# ab_v10_panel.net
KiCad netlist of a schematic drawn in EAGLE
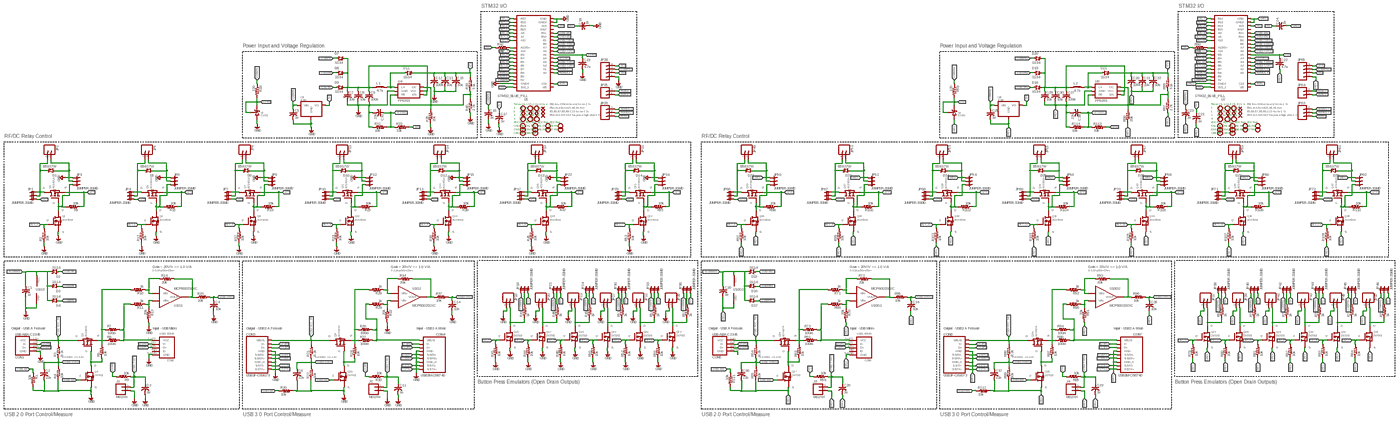
[diagram p0: schematic, sheet 1, overview]
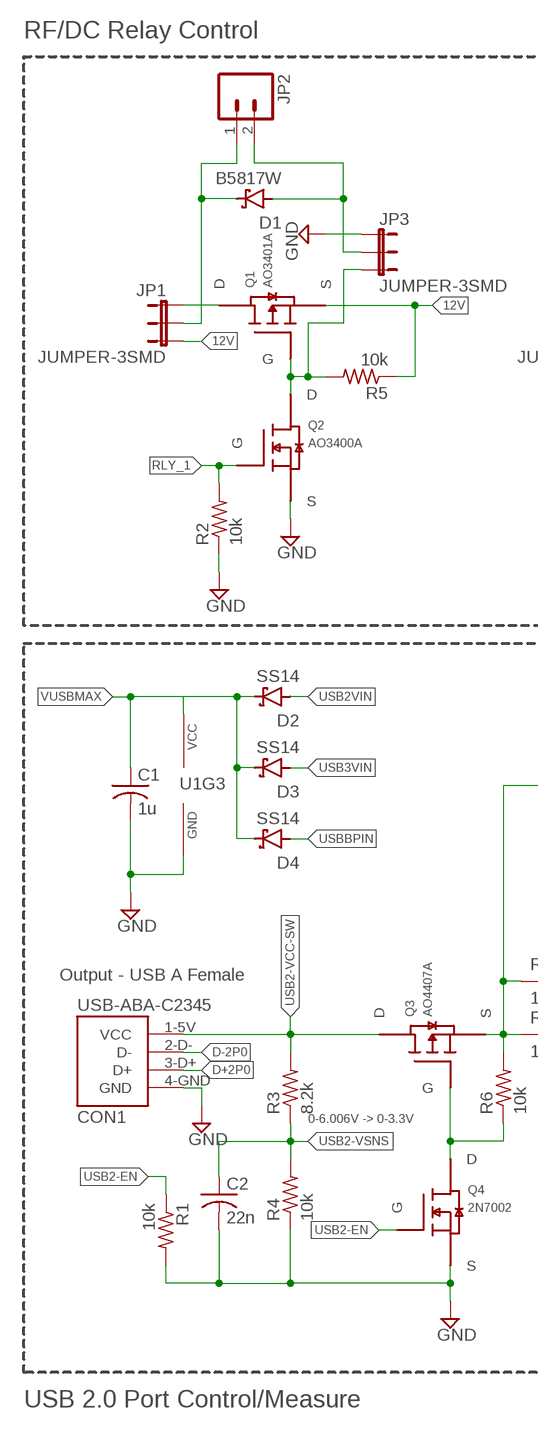
[diagram p1: schematic, sheet 1, part 1 of 4]
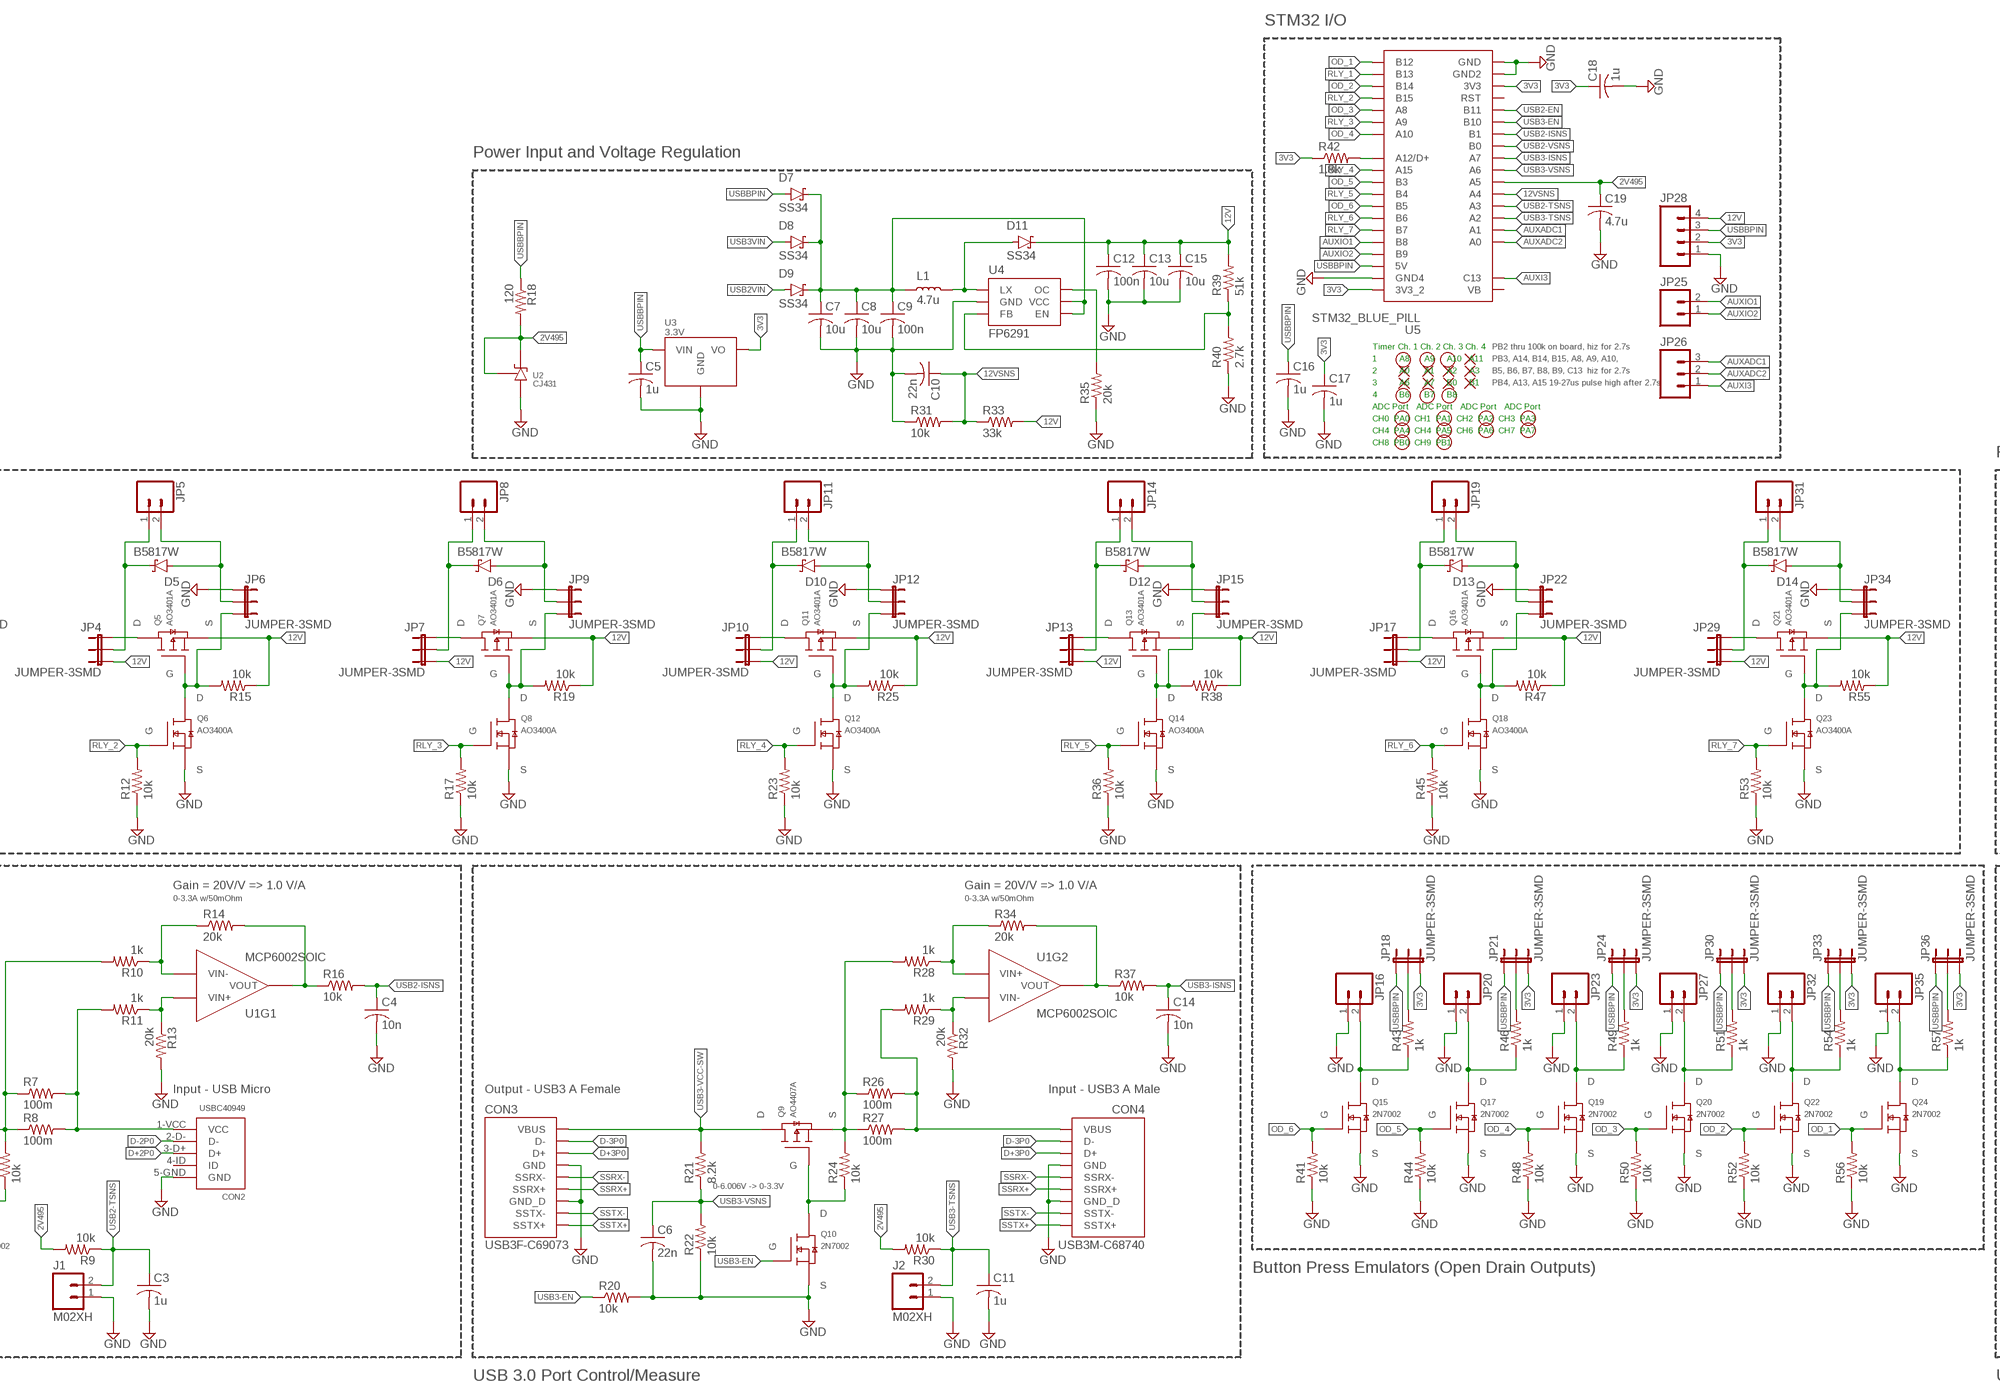
[diagram p2: schematic, sheet 1, part 2 of 4]
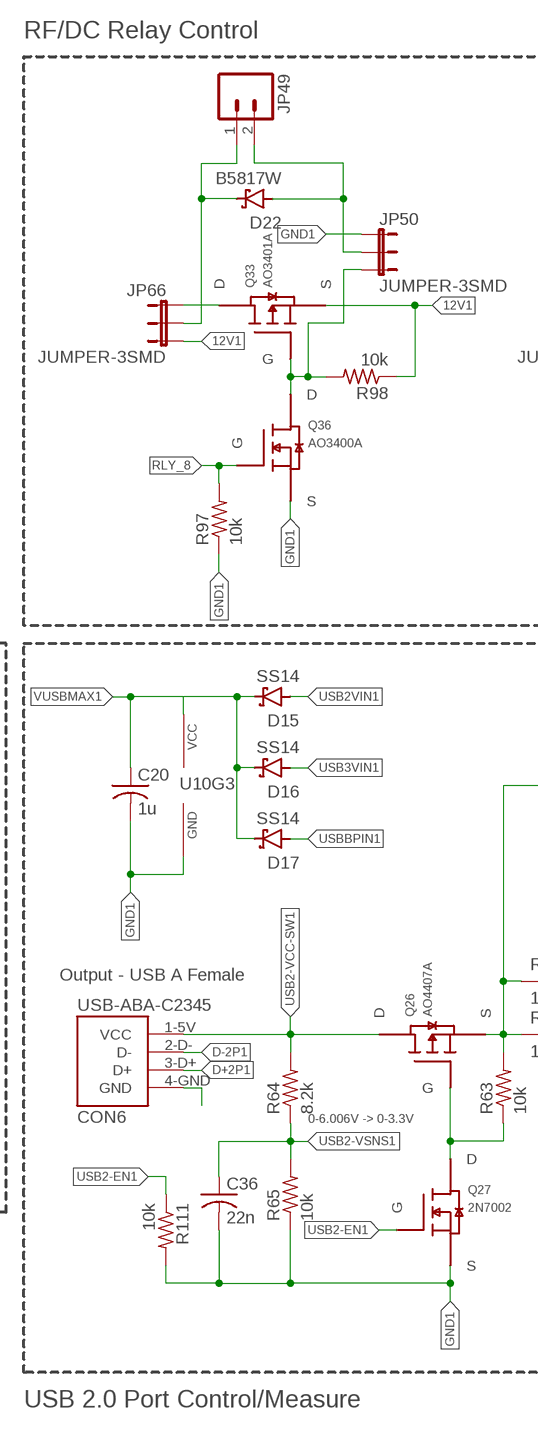
[diagram p3: schematic, sheet 1, part 3 of 4]
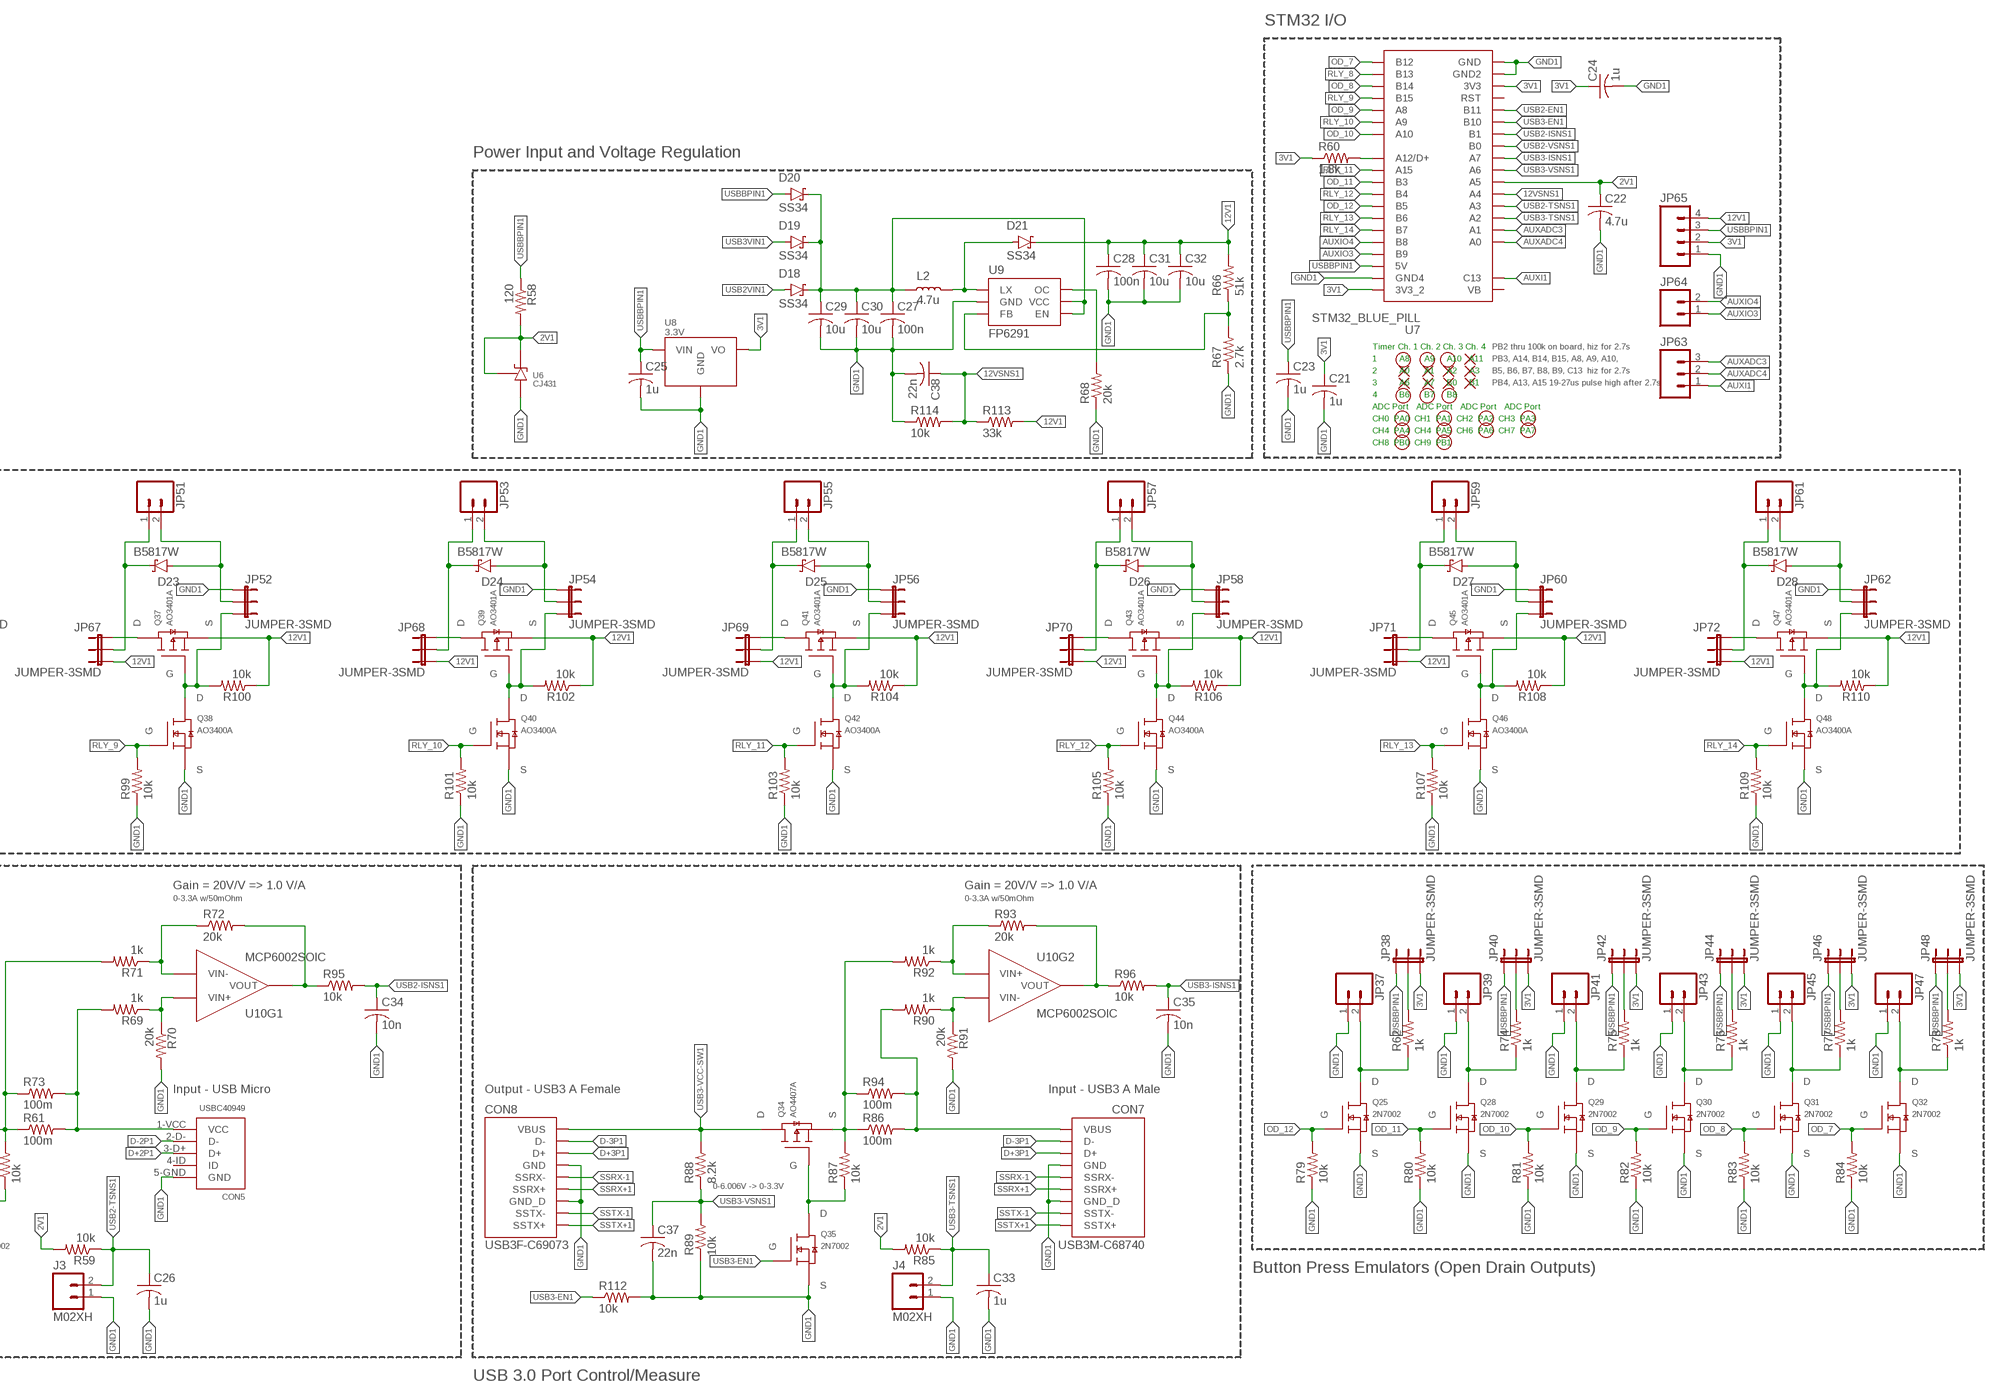
[diagram p4: schematic, sheet 1, part 4 of 4]

(export (version "E")
  (design (tool "Eeschema 10.0.6"))
  (components
    (comp (ref "C1")
      (value "1u")
      (footprint "eagle-import:C0402")
      (libsource (lib "eagle-import") (part "C-USC0402"))
    )
    (comp (ref "C2")
      (value "22n")
      (footprint "eagle-import:C0402")
      (libsource (lib "eagle-import") (part "C-USC0402"))
    )
    (comp (ref "C3")
      (value "1u")
      (footprint "eagle-import:C0402")
      (libsource (lib "eagle-import") (part "C-USC0402"))
    )
    (comp (ref "C4")
      (value "10n")
      (footprint "eagle-import:C0402")
      (libsource (lib "eagle-import") (part "C-USC0402"))
    )
    (comp (ref "C5")
      (value "1u")
      (footprint "eagle-import:C0402")
      (libsource (lib "eagle-import") (part "C-USC0402"))
    )
    (comp (ref "C6")
      (value "22n")
      (footprint "eagle-import:C0402")
      (libsource (lib "eagle-import") (part "C-USC0402"))
    )
    (comp (ref "C7")
      (value "10u")
      (footprint "eagle-import:C0603")
      (libsource (lib "eagle-import") (part "C-USC0603"))
    )
    (comp (ref "C8")
      (value "10u")
      (footprint "eagle-import:C0603")
      (libsource (lib "eagle-import") (part "C-USC0603"))
    )
    (comp (ref "C9")
      (value "100n")
      (footprint "eagle-import:C0402")
      (libsource (lib "eagle-import") (part "C-USC0402"))
    )
    (comp (ref "C10")
      (value "22n")
      (footprint "eagle-import:C0402")
      (libsource (lib "eagle-import") (part "C-USC0402"))
    )
    (comp (ref "C11")
      (value "1u")
      (footprint "eagle-import:C0402")
      (libsource (lib "eagle-import") (part "C-USC0402"))
    )
    (comp (ref "C12")
      (value "100n")
      (footprint "eagle-import:C0402")
      (libsource (lib "eagle-import") (part "C-USC0402"))
    )
    (comp (ref "C13")
      (value "10u")
      (footprint "eagle-import:C0805")
      (libsource (lib "eagle-import") (part "C-USC0805"))
    )
    (comp (ref "C14")
      (value "10n")
      (footprint "eagle-import:C0402")
      (libsource (lib "eagle-import") (part "C-USC0402"))
    )
    (comp (ref "C15")
      (value "10u")
      (footprint "eagle-import:C0805")
      (libsource (lib "eagle-import") (part "C-USC0805"))
    )
    (comp (ref "C16")
      (value "1u")
      (footprint "eagle-import:C0402")
      (libsource (lib "eagle-import") (part "C-USC0402"))
    )
    (comp (ref "C17")
      (value "1u")
      (footprint "eagle-import:C0402")
      (libsource (lib "eagle-import") (part "C-USC0402"))
    )
    (comp (ref "C18")
      (value "1u")
      (footprint "eagle-import:C0402")
      (libsource (lib "eagle-import") (part "C-USC0402"))
    )
    (comp (ref "C19")
      (value "4.7u")
      (footprint "eagle-import:C0402")
      (libsource (lib "eagle-import") (part "C-USC0402"))
    )
    (comp (ref "C20")
      (value "1u")
      (footprint "eagle-import:C0402")
      (libsource (lib "eagle-import") (part "C-USC0402"))
    )
    (comp (ref "C21")
      (value "1u")
      (footprint "eagle-import:C0402")
      (libsource (lib "eagle-import") (part "C-USC0402"))
    )
    (comp (ref "C22")
      (value "4.7u")
      (footprint "eagle-import:C0402")
      (libsource (lib "eagle-import") (part "C-USC0402"))
    )
    (comp (ref "C23")
      (value "1u")
      (footprint "eagle-import:C0402")
      (libsource (lib "eagle-import") (part "C-USC0402"))
    )
    (comp (ref "C24")
      (value "1u")
      (footprint "eagle-import:C0402")
      (libsource (lib "eagle-import") (part "C-USC0402"))
    )
    (comp (ref "C25")
      (value "1u")
      (footprint "eagle-import:C0402")
      (libsource (lib "eagle-import") (part "C-USC0402"))
    )
    (comp (ref "C26")
      (value "1u")
      (footprint "eagle-import:C0402")
      (libsource (lib "eagle-import") (part "C-USC0402"))
    )
    (comp (ref "C27")
      (value "100n")
      (footprint "eagle-import:C0402")
      (libsource (lib "eagle-import") (part "C-USC0402"))
    )
    (comp (ref "C28")
      (value "100n")
      (footprint "eagle-import:C0402")
      (libsource (lib "eagle-import") (part "C-USC0402"))
    )
    (comp (ref "C29")
      (value "10u")
      (footprint "eagle-import:C0603")
      (libsource (lib "eagle-import") (part "C-USC0603"))
    )
    (comp (ref "C30")
      (value "10u")
      (footprint "eagle-import:C0603")
      (libsource (lib "eagle-import") (part "C-USC0603"))
    )
    (comp (ref "C31")
      (value "10u")
      (footprint "eagle-import:C0805")
      (libsource (lib "eagle-import") (part "C-USC0805"))
    )
    (comp (ref "C32")
      (value "10u")
      (footprint "eagle-import:C0805")
      (libsource (lib "eagle-import") (part "C-USC0805"))
    )
    (comp (ref "C33")
      (value "1u")
      (footprint "eagle-import:C0402")
      (libsource (lib "eagle-import") (part "C-USC0402"))
    )
    (comp (ref "C34")
      (value "10n")
      (footprint "eagle-import:C0402")
      (libsource (lib "eagle-import") (part "C-USC0402"))
    )
    (comp (ref "C35")
      (value "10n")
      (footprint "eagle-import:C0402")
      (libsource (lib "eagle-import") (part "C-USC0402"))
    )
    (comp (ref "C36")
      (value "22n")
      (footprint "eagle-import:C0402")
      (libsource (lib "eagle-import") (part "C-USC0402"))
    )
    (comp (ref "C37")
      (value "22n")
      (footprint "eagle-import:C0402")
      (libsource (lib "eagle-import") (part "C-USC0402"))
    )
    (comp (ref "C38")
      (value "22n")
      (footprint "eagle-import:C0402")
      (libsource (lib "eagle-import") (part "C-USC0402"))
    )
    (comp (ref "CON1")
      (value "USB-ABA-C2345")
      (footprint "eagle-import:USB_A_C2345")
      (libsource (lib "eagle-import") (part "USB-ABA-C2345"))
    )
    (comp (ref "CON2")
      (value "USBC40949")
      (footprint "eagle-import:MICRO_USB-B_C40949")
      (libsource (lib "eagle-import") (part "USBC40949"))
    )
    (comp (ref "CON3")
      (value "USB3F-C69073")
      (footprint "eagle-import:USB3-F-C69073")
      (libsource (lib "eagle-import") (part "USB3F-C69073"))
    )
    (comp (ref "CON4")
      (value "USB3M-C68740")
      (footprint "eagle-import:USB3-M-C68740")
      (libsource (lib "eagle-import") (part "USB3M-C68740"))
    )
    (comp (ref "CON5")
      (value "USBC40949")
      (footprint "eagle-import:MICRO_USB-B_C40949")
      (libsource (lib "eagle-import") (part "USBC40949"))
    )
    (comp (ref "CON6")
      (value "USB-ABA-C2345")
      (footprint "eagle-import:USB_A_C2345")
      (libsource (lib "eagle-import") (part "USB-ABA-C2345"))
    )
    (comp (ref "CON7")
      (value "USB3M-C68740")
      (footprint "eagle-import:USB3-M-C68740")
      (libsource (lib "eagle-import") (part "USB3M-C68740"))
    )
    (comp (ref "CON8")
      (value "USB3F-C69073")
      (footprint "eagle-import:USB3-F-C69073")
      (libsource (lib "eagle-import") (part "USB3F-C69073"))
    )
    (comp (ref "D1")
      (value "B5817W")
      (footprint "eagle-import:SOD123W")
      (libsource (lib "eagle-import") (part "PMEG3020ER"))
    )
    (comp (ref "D2")
      (value "SS14")
      (footprint "eagle-import:SMA")
      (libsource (lib "eagle-import") (part "DIODE_SCHOTTKY_SMSSMA"))
    )
    (comp (ref "D3")
      (value "SS14")
      (footprint "eagle-import:SMA")
      (libsource (lib "eagle-import") (part "DIODE_SCHOTTKY_SMSSMA"))
    )
    (comp (ref "D4")
      (value "SS14")
      (footprint "eagle-import:SMA")
      (libsource (lib "eagle-import") (part "DIODE_SCHOTTKY_SMSSMA"))
    )
    (comp (ref "D5")
      (value "B5817W")
      (footprint "eagle-import:SOD123W")
      (libsource (lib "eagle-import") (part "PMEG3020ER"))
    )
    (comp (ref "D6")
      (value "B5817W")
      (footprint "eagle-import:SOD123W")
      (libsource (lib "eagle-import") (part "PMEG3020ER"))
    )
    (comp (ref "D7")
      (value "SS34")
      (footprint "eagle-import:SMA")
      (libsource (lib "eagle-import") (part "DIODE_SCHOTTKY_SMSSMA"))
    )
    (comp (ref "D8")
      (value "SS34")
      (footprint "eagle-import:SMA")
      (libsource (lib "eagle-import") (part "DIODE_SCHOTTKY_SMSSMA"))
    )
    (comp (ref "D9")
      (value "SS34")
      (footprint "eagle-import:SMA")
      (libsource (lib "eagle-import") (part "DIODE_SCHOTTKY_SMSSMA"))
    )
    (comp (ref "D10")
      (value "B5817W")
      (footprint "eagle-import:SOD123W")
      (libsource (lib "eagle-import") (part "PMEG3020ER"))
    )
    (comp (ref "D11")
      (value "SS34")
      (footprint "eagle-import:SMA")
      (libsource (lib "eagle-import") (part "DIODE_SCHOTTKY_SMSSMA"))
    )
    (comp (ref "D12")
      (value "B5817W")
      (footprint "eagle-import:SOD123W")
      (libsource (lib "eagle-import") (part "PMEG3020ER"))
    )
    (comp (ref "D13")
      (value "B5817W")
      (footprint "eagle-import:SOD123W")
      (libsource (lib "eagle-import") (part "PMEG3020ER"))
    )
    (comp (ref "D14")
      (value "B5817W")
      (footprint "eagle-import:SOD123W")
      (libsource (lib "eagle-import") (part "PMEG3020ER"))
    )
    (comp (ref "D15")
      (value "SS14")
      (footprint "eagle-import:SMA")
      (libsource (lib "eagle-import") (part "DIODE_SCHOTTKY_SMSSMA"))
    )
    (comp (ref "D16")
      (value "SS14")
      (footprint "eagle-import:SMA")
      (libsource (lib "eagle-import") (part "DIODE_SCHOTTKY_SMSSMA"))
    )
    (comp (ref "D17")
      (value "SS14")
      (footprint "eagle-import:SMA")
      (libsource (lib "eagle-import") (part "DIODE_SCHOTTKY_SMSSMA"))
    )
    (comp (ref "D18")
      (value "SS34")
      (footprint "eagle-import:SMA")
      (libsource (lib "eagle-import") (part "DIODE_SCHOTTKY_SMSSMA"))
    )
    (comp (ref "D19")
      (value "SS34")
      (footprint "eagle-import:SMA")
      (libsource (lib "eagle-import") (part "DIODE_SCHOTTKY_SMSSMA"))
    )
    (comp (ref "D20")
      (value "SS34")
      (footprint "eagle-import:SMA")
      (libsource (lib "eagle-import") (part "DIODE_SCHOTTKY_SMSSMA"))
    )
    (comp (ref "D21")
      (value "SS34")
      (footprint "eagle-import:SMA")
      (libsource (lib "eagle-import") (part "DIODE_SCHOTTKY_SMSSMA"))
    )
    (comp (ref "D22")
      (value "B5817W")
      (footprint "eagle-import:SOD123W")
      (libsource (lib "eagle-import") (part "PMEG3020ER"))
    )
    (comp (ref "D23")
      (value "B5817W")
      (footprint "eagle-import:SOD123W")
      (libsource (lib "eagle-import") (part "PMEG3020ER"))
    )
    (comp (ref "D24")
      (value "B5817W")
      (footprint "eagle-import:SOD123W")
      (libsource (lib "eagle-import") (part "PMEG3020ER"))
    )
    (comp (ref "D25")
      (value "B5817W")
      (footprint "eagle-import:SOD123W")
      (libsource (lib "eagle-import") (part "PMEG3020ER"))
    )
    (comp (ref "D26")
      (value "B5817W")
      (footprint "eagle-import:SOD123W")
      (libsource (lib "eagle-import") (part "PMEG3020ER"))
    )
    (comp (ref "D27")
      (value "B5817W")
      (footprint "eagle-import:SOD123W")
      (libsource (lib "eagle-import") (part "PMEG3020ER"))
    )
    (comp (ref "D28")
      (value "B5817W")
      (footprint "eagle-import:SOD123W")
      (libsource (lib "eagle-import") (part "PMEG3020ER"))
    )
    (comp (ref "J1")
      (value "M02XH")
      (footprint "eagle-import:B2B-XH-A")
      (libsource (lib "eagle-import") (part "M02XH"))
    )
    (comp (ref "J2")
      (value "M02XH")
      (footprint "eagle-import:B2B-XH-A")
      (libsource (lib "eagle-import") (part "M02XH"))
    )
    (comp (ref "J3")
      (value "M02XH")
      (footprint "eagle-import:B2B-XH-A")
      (libsource (lib "eagle-import") (part "M02XH"))
    )
    (comp (ref "J4")
      (value "M02XH")
      (footprint "eagle-import:B2B-XH-A")
      (libsource (lib "eagle-import") (part "M02XH"))
    )
    (comp (ref "JP1")
      (value "JUMPER-3SMD")
      (footprint "eagle-import:SJ_3")
      (libsource (lib "eagle-import") (part "JUMPER-3SMD"))
    )
    (comp (ref "JP2")
      (value "M02PTH")
      (footprint "eagle-import:1X02")
      (libsource (lib "eagle-import") (part "M02PTH"))
    )
    (comp (ref "JP3")
      (value "JUMPER-3SMD")
      (footprint "eagle-import:SJ_3")
      (libsource (lib "eagle-import") (part "JUMPER-3SMD"))
    )
    (comp (ref "JP4")
      (value "JUMPER-3SMD")
      (footprint "eagle-import:SJ_3")
      (libsource (lib "eagle-import") (part "JUMPER-3SMD"))
    )
    (comp (ref "JP5")
      (value "M02PTH")
      (footprint "eagle-import:1X02")
      (libsource (lib "eagle-import") (part "M02PTH"))
    )
    (comp (ref "JP6")
      (value "JUMPER-3SMD")
      (footprint "eagle-import:SJ_3")
      (libsource (lib "eagle-import") (part "JUMPER-3SMD"))
    )
    (comp (ref "JP7")
      (value "JUMPER-3SMD")
      (footprint "eagle-import:SJ_3")
      (libsource (lib "eagle-import") (part "JUMPER-3SMD"))
    )
    (comp (ref "JP8")
      (value "M02PTH")
      (footprint "eagle-import:1X02")
      (libsource (lib "eagle-import") (part "M02PTH"))
    )
    (comp (ref "JP9")
      (value "JUMPER-3SMD")
      (footprint "eagle-import:SJ_3")
      (libsource (lib "eagle-import") (part "JUMPER-3SMD"))
    )
    (comp (ref "JP10")
      (value "JUMPER-3SMD")
      (footprint "eagle-import:SJ_3")
      (libsource (lib "eagle-import") (part "JUMPER-3SMD"))
    )
    (comp (ref "JP11")
      (value "M02PTH")
      (footprint "eagle-import:1X02")
      (libsource (lib "eagle-import") (part "M02PTH"))
    )
    (comp (ref "JP12")
      (value "JUMPER-3SMD")
      (footprint "eagle-import:SJ_3")
      (libsource (lib "eagle-import") (part "JUMPER-3SMD"))
    )
    (comp (ref "JP13")
      (value "JUMPER-3SMD")
      (footprint "eagle-import:SJ_3")
      (libsource (lib "eagle-import") (part "JUMPER-3SMD"))
    )
    (comp (ref "JP14")
      (value "M02PTH")
      (footprint "eagle-import:1X02")
      (libsource (lib "eagle-import") (part "M02PTH"))
    )
    (comp (ref "JP15")
      (value "JUMPER-3SMD")
      (footprint "eagle-import:SJ_3")
      (libsource (lib "eagle-import") (part "JUMPER-3SMD"))
    )
    (comp (ref "JP16")
      (value "M02PTH")
      (footprint "eagle-import:1X02")
      (libsource (lib "eagle-import") (part "M02PTH"))
    )
    (comp (ref "JP17")
      (value "JUMPER-3SMD")
      (footprint "eagle-import:SJ_3")
      (libsource (lib "eagle-import") (part "JUMPER-3SMD"))
    )
    (comp (ref "JP18")
      (value "JUMPER-3SMD")
      (footprint "eagle-import:SJ_3")
      (libsource (lib "eagle-import") (part "JUMPER-3SMD"))
    )
    (comp (ref "JP19")
      (value "M02PTH")
      (footprint "eagle-import:1X02")
      (libsource (lib "eagle-import") (part "M02PTH"))
    )
    (comp (ref "JP20")
      (value "M02PTH")
      (footprint "eagle-import:1X02")
      (libsource (lib "eagle-import") (part "M02PTH"))
    )
    (comp (ref "JP21")
      (value "JUMPER-3SMD")
      (footprint "eagle-import:SJ_3")
      (libsource (lib "eagle-import") (part "JUMPER-3SMD"))
    )
    (comp (ref "JP22")
      (value "JUMPER-3SMD")
      (footprint "eagle-import:SJ_3")
      (libsource (lib "eagle-import") (part "JUMPER-3SMD"))
    )
    (comp (ref "JP23")
      (value "M02PTH")
      (footprint "eagle-import:1X02")
      (libsource (lib "eagle-import") (part "M02PTH"))
    )
    (comp (ref "JP24")
      (value "JUMPER-3SMD")
      (footprint "eagle-import:SJ_3")
      (libsource (lib "eagle-import") (part "JUMPER-3SMD"))
    )
    (comp (ref "JP25")
      (value "M02PTH")
      (footprint "eagle-import:1X02")
      (libsource (lib "eagle-import") (part "M02PTH"))
    )
    (comp (ref "JP26")
      (value "M03PTH")
      (footprint "eagle-import:1X03")
      (libsource (lib "eagle-import") (part "M03PTH"))
    )
    (comp (ref "JP27")
      (value "M02PTH")
      (footprint "eagle-import:1X02")
      (libsource (lib "eagle-import") (part "M02PTH"))
    )
    (comp (ref "JP28")
      (value "M04PTH")
      (footprint "eagle-import:1X04")
      (libsource (lib "eagle-import") (part "M04PTH"))
    )
    (comp (ref "JP29")
      (value "JUMPER-3SMD")
      (footprint "eagle-import:SJ_3")
      (libsource (lib "eagle-import") (part "JUMPER-3SMD"))
    )
    (comp (ref "JP30")
      (value "JUMPER-3SMD")
      (footprint "eagle-import:SJ_3")
      (libsource (lib "eagle-import") (part "JUMPER-3SMD"))
    )
    (comp (ref "JP31")
      (value "M02PTH")
      (footprint "eagle-import:1X02")
      (libsource (lib "eagle-import") (part "M02PTH"))
    )
    (comp (ref "JP32")
      (value "M02PTH")
      (footprint "eagle-import:1X02")
      (libsource (lib "eagle-import") (part "M02PTH"))
    )
    (comp (ref "JP33")
      (value "JUMPER-3SMD")
      (footprint "eagle-import:SJ_3")
      (libsource (lib "eagle-import") (part "JUMPER-3SMD"))
    )
    (comp (ref "JP34")
      (value "JUMPER-3SMD")
      (footprint "eagle-import:SJ_3")
      (libsource (lib "eagle-import") (part "JUMPER-3SMD"))
    )
    (comp (ref "JP35")
      (value "M02PTH")
      (footprint "eagle-import:1X02")
      (libsource (lib "eagle-import") (part "M02PTH"))
    )
    (comp (ref "JP36")
      (value "JUMPER-3SMD")
      (footprint "eagle-import:SJ_3")
      (libsource (lib "eagle-import") (part "JUMPER-3SMD"))
    )
    (comp (ref "JP37")
      (value "M02PTH")
      (footprint "eagle-import:1X02")
      (libsource (lib "eagle-import") (part "M02PTH"))
    )
    (comp (ref "JP38")
      (value "JUMPER-3SMD")
      (footprint "eagle-import:SJ_3")
      (libsource (lib "eagle-import") (part "JUMPER-3SMD"))
    )
    (comp (ref "JP39")
      (value "M02PTH")
      (footprint "eagle-import:1X02")
      (libsource (lib "eagle-import") (part "M02PTH"))
    )
    (comp (ref "JP40")
      (value "JUMPER-3SMD")
      (footprint "eagle-import:SJ_3")
      (libsource (lib "eagle-import") (part "JUMPER-3SMD"))
    )
    (comp (ref "JP41")
      (value "M02PTH")
      (footprint "eagle-import:1X02")
      (libsource (lib "eagle-import") (part "M02PTH"))
    )
    (comp (ref "JP42")
      (value "JUMPER-3SMD")
      (footprint "eagle-import:SJ_3")
      (libsource (lib "eagle-import") (part "JUMPER-3SMD"))
    )
    (comp (ref "JP43")
      (value "M02PTH")
      (footprint "eagle-import:1X02")
      (libsource (lib "eagle-import") (part "M02PTH"))
    )
    (comp (ref "JP44")
      (value "JUMPER-3SMD")
      (footprint "eagle-import:SJ_3")
      (libsource (lib "eagle-import") (part "JUMPER-3SMD"))
    )
    (comp (ref "JP45")
      (value "M02PTH")
      (footprint "eagle-import:1X02")
      (libsource (lib "eagle-import") (part "M02PTH"))
    )
    (comp (ref "JP46")
      (value "JUMPER-3SMD")
      (footprint "eagle-import:SJ_3")
      (libsource (lib "eagle-import") (part "JUMPER-3SMD"))
    )
    (comp (ref "JP47")
      (value "M02PTH")
      (footprint "eagle-import:1X02")
      (libsource (lib "eagle-import") (part "M02PTH"))
    )
    (comp (ref "JP48")
      (value "JUMPER-3SMD")
      (footprint "eagle-import:SJ_3")
      (libsource (lib "eagle-import") (part "JUMPER-3SMD"))
    )
    (comp (ref "JP49")
      (value "M02PTH")
      (footprint "eagle-import:1X02")
      (libsource (lib "eagle-import") (part "M02PTH"))
    )
    (comp (ref "JP50")
      (value "JUMPER-3SMD")
      (footprint "eagle-import:SJ_3")
      (libsource (lib "eagle-import") (part "JUMPER-3SMD"))
    )
    (comp (ref "JP51")
      (value "M02PTH")
      (footprint "eagle-import:1X02")
      (libsource (lib "eagle-import") (part "M02PTH"))
    )
    (comp (ref "JP52")
      (value "JUMPER-3SMD")
      (footprint "eagle-import:SJ_3")
      (libsource (lib "eagle-import") (part "JUMPER-3SMD"))
    )
    (comp (ref "JP53")
      (value "M02PTH")
      (footprint "eagle-import:1X02")
      (libsource (lib "eagle-import") (part "M02PTH"))
    )
    (comp (ref "JP54")
      (value "JUMPER-3SMD")
      (footprint "eagle-import:SJ_3")
      (libsource (lib "eagle-import") (part "JUMPER-3SMD"))
    )
    (comp (ref "JP55")
      (value "M02PTH")
      (footprint "eagle-import:1X02")
      (libsource (lib "eagle-import") (part "M02PTH"))
    )
    (comp (ref "JP56")
      (value "JUMPER-3SMD")
      (footprint "eagle-import:SJ_3")
      (libsource (lib "eagle-import") (part "JUMPER-3SMD"))
    )
    (comp (ref "JP57")
      (value "M02PTH")
      (footprint "eagle-import:1X02")
      (libsource (lib "eagle-import") (part "M02PTH"))
    )
    (comp (ref "JP58")
      (value "JUMPER-3SMD")
      (footprint "eagle-import:SJ_3")
      (libsource (lib "eagle-import") (part "JUMPER-3SMD"))
    )
    (comp (ref "JP59")
      (value "M02PTH")
      (footprint "eagle-import:1X02")
      (libsource (lib "eagle-import") (part "M02PTH"))
    )
    (comp (ref "JP60")
      (value "JUMPER-3SMD")
      (footprint "eagle-import:SJ_3")
      (libsource (lib "eagle-import") (part "JUMPER-3SMD"))
    )
    (comp (ref "JP61")
      (value "M02PTH")
      (footprint "eagle-import:1X02")
      (libsource (lib "eagle-import") (part "M02PTH"))
    )
    (comp (ref "JP62")
      (value "JUMPER-3SMD")
      (footprint "eagle-import:SJ_3")
      (libsource (lib "eagle-import") (part "JUMPER-3SMD"))
    )
    (comp (ref "JP63")
      (value "M03PTH")
      (footprint "eagle-import:1X03")
      (libsource (lib "eagle-import") (part "M03PTH"))
    )
    (comp (ref "JP64")
      (value "M02PTH")
      (footprint "eagle-import:1X02")
      (libsource (lib "eagle-import") (part "M02PTH"))
    )
    (comp (ref "JP65")
      (value "M04PTH")
      (footprint "eagle-import:1X04")
      (libsource (lib "eagle-import") (part "M04PTH"))
    )
    (comp (ref "JP66")
      (value "JUMPER-3SMD")
      (footprint "eagle-import:SJ_3")
      (libsource (lib "eagle-import") (part "JUMPER-3SMD"))
    )
    (comp (ref "JP67")
      (value "JUMPER-3SMD")
      (footprint "eagle-import:SJ_3")
      (libsource (lib "eagle-import") (part "JUMPER-3SMD"))
    )
    (comp (ref "JP68")
      (value "JUMPER-3SMD")
      (footprint "eagle-import:SJ_3")
      (libsource (lib "eagle-import") (part "JUMPER-3SMD"))
    )
    (comp (ref "JP69")
      (value "JUMPER-3SMD")
      (footprint "eagle-import:SJ_3")
      (libsource (lib "eagle-import") (part "JUMPER-3SMD"))
    )
    (comp (ref "JP70")
      (value "JUMPER-3SMD")
      (footprint "eagle-import:SJ_3")
      (libsource (lib "eagle-import") (part "JUMPER-3SMD"))
    )
    (comp (ref "JP71")
      (value "JUMPER-3SMD")
      (footprint "eagle-import:SJ_3")
      (libsource (lib "eagle-import") (part "JUMPER-3SMD"))
    )
    (comp (ref "JP72")
      (value "JUMPER-3SMD")
      (footprint "eagle-import:SJ_3")
      (libsource (lib "eagle-import") (part "JUMPER-3SMD"))
    )
    (comp (ref "L1")
      (value "4.7u")
      (footprint "eagle-import:INDUCTOR_6X6")
      (libsource (lib "eagle-import") (part "INDUCTOR6X6"))
    )
    (comp (ref "L2")
      (value "4.7u")
      (footprint "eagle-import:INDUCTOR_6X6")
      (libsource (lib "eagle-import") (part "INDUCTOR6X6"))
    )
    (comp (ref "Q1")
      (value "AO3401A")
      (footprint "eagle-import:SOT23")
      (libsource (lib "eagle-import") (part "AO3401A"))
    )
    (comp (ref "Q2")
      (value "AO3400A")
      (footprint "eagle-import:SOT23")
      (libsource (lib "eagle-import") (part "2N7002P"))
    )
    (comp (ref "Q3")
      (value "AO4407A")
      (footprint "eagle-import:8-SOIC")
      (libsource (lib "eagle-import") (part "P-MOSFET-SOIC8"))
    )
    (comp (ref "Q4")
      (value "2N7002")
      (footprint "eagle-import:SOT23")
      (libsource (lib "eagle-import") (part "2N7002P"))
    )
    (comp (ref "Q5")
      (value "AO3401A")
      (footprint "eagle-import:SOT23")
      (libsource (lib "eagle-import") (part "AO3401A"))
    )
    (comp (ref "Q6")
      (value "AO3400A")
      (footprint "eagle-import:SOT23")
      (libsource (lib "eagle-import") (part "2N7002P"))
    )
    (comp (ref "Q7")
      (value "AO3401A")
      (footprint "eagle-import:SOT23")
      (libsource (lib "eagle-import") (part "AO3401A"))
    )
    (comp (ref "Q8")
      (value "AO3400A")
      (footprint "eagle-import:SOT23")
      (libsource (lib "eagle-import") (part "2N7002P"))
    )
    (comp (ref "Q9")
      (value "AO4407A")
      (footprint "eagle-import:8-SOIC")
      (libsource (lib "eagle-import") (part "P-MOSFET-SOIC8"))
    )
    (comp (ref "Q10")
      (value "2N7002")
      (footprint "eagle-import:SOT23")
      (libsource (lib "eagle-import") (part "2N7002P"))
    )
    (comp (ref "Q11")
      (value "AO3401A")
      (footprint "eagle-import:SOT23")
      (libsource (lib "eagle-import") (part "AO3401A"))
    )
    (comp (ref "Q12")
      (value "AO3400A")
      (footprint "eagle-import:SOT23")
      (libsource (lib "eagle-import") (part "2N7002P"))
    )
    (comp (ref "Q13")
      (value "AO3401A")
      (footprint "eagle-import:SOT23")
      (libsource (lib "eagle-import") (part "AO3401A"))
    )
    (comp (ref "Q14")
      (value "AO3400A")
      (footprint "eagle-import:SOT23")
      (libsource (lib "eagle-import") (part "2N7002P"))
    )
    (comp (ref "Q15")
      (value "2N7002")
      (footprint "eagle-import:SOT23")
      (libsource (lib "eagle-import") (part "2N7002P"))
    )
    (comp (ref "Q16")
      (value "AO3401A")
      (footprint "eagle-import:SOT23")
      (libsource (lib "eagle-import") (part "AO3401A"))
    )
    (comp (ref "Q17")
      (value "2N7002")
      (footprint "eagle-import:SOT23")
      (libsource (lib "eagle-import") (part "2N7002P"))
    )
    (comp (ref "Q18")
      (value "AO3400A")
      (footprint "eagle-import:SOT23")
      (libsource (lib "eagle-import") (part "2N7002P"))
    )
    (comp (ref "Q19")
      (value "2N7002")
      (footprint "eagle-import:SOT23")
      (libsource (lib "eagle-import") (part "2N7002P"))
    )
    (comp (ref "Q20")
      (value "2N7002")
      (footprint "eagle-import:SOT23")
      (libsource (lib "eagle-import") (part "2N7002P"))
    )
    (comp (ref "Q21")
      (value "AO3401A")
      (footprint "eagle-import:SOT23")
      (libsource (lib "eagle-import") (part "AO3401A"))
    )
    (comp (ref "Q22")
      (value "2N7002")
      (footprint "eagle-import:SOT23")
      (libsource (lib "eagle-import") (part "2N7002P"))
    )
    (comp (ref "Q23")
      (value "AO3400A")
      (footprint "eagle-import:SOT23")
      (libsource (lib "eagle-import") (part "2N7002P"))
    )
    (comp (ref "Q24")
      (value "2N7002")
      (footprint "eagle-import:SOT23")
      (libsource (lib "eagle-import") (part "2N7002P"))
    )
    (comp (ref "Q25")
      (value "2N7002")
      (footprint "eagle-import:SOT23")
      (libsource (lib "eagle-import") (part "2N7002P"))
    )
    (comp (ref "Q26")
      (value "AO4407A")
      (footprint "eagle-import:8-SOIC")
      (libsource (lib "eagle-import") (part "P-MOSFET-SOIC8"))
    )
    (comp (ref "Q27")
      (value "2N7002")
      (footprint "eagle-import:SOT23")
      (libsource (lib "eagle-import") (part "2N7002P"))
    )
    (comp (ref "Q28")
      (value "2N7002")
      (footprint "eagle-import:SOT23")
      (libsource (lib "eagle-import") (part "2N7002P"))
    )
    (comp (ref "Q29")
      (value "2N7002")
      (footprint "eagle-import:SOT23")
      (libsource (lib "eagle-import") (part "2N7002P"))
    )
    (comp (ref "Q30")
      (value "2N7002")
      (footprint "eagle-import:SOT23")
      (libsource (lib "eagle-import") (part "2N7002P"))
    )
    (comp (ref "Q31")
      (value "2N7002")
      (footprint "eagle-import:SOT23")
      (libsource (lib "eagle-import") (part "2N7002P"))
    )
    (comp (ref "Q32")
      (value "2N7002")
      (footprint "eagle-import:SOT23")
      (libsource (lib "eagle-import") (part "2N7002P"))
    )
    (comp (ref "Q33")
      (value "AO3401A")
      (footprint "eagle-import:SOT23")
      (libsource (lib "eagle-import") (part "AO3401A"))
    )
    (comp (ref "Q34")
      (value "AO4407A")
      (footprint "eagle-import:8-SOIC")
      (libsource (lib "eagle-import") (part "P-MOSFET-SOIC8"))
    )
    (comp (ref "Q35")
      (value "2N7002")
      (footprint "eagle-import:SOT23")
      (libsource (lib "eagle-import") (part "2N7002P"))
    )
    (comp (ref "Q36")
      (value "AO3400A")
      (footprint "eagle-import:SOT23")
      (libsource (lib "eagle-import") (part "2N7002P"))
    )
    (comp (ref "Q37")
      (value "AO3401A")
      (footprint "eagle-import:SOT23")
      (libsource (lib "eagle-import") (part "AO3401A"))
    )
    (comp (ref "Q38")
      (value "AO3400A")
      (footprint "eagle-import:SOT23")
      (libsource (lib "eagle-import") (part "2N7002P"))
    )
    (comp (ref "Q39")
      (value "AO3401A")
      (footprint "eagle-import:SOT23")
      (libsource (lib "eagle-import") (part "AO3401A"))
    )
    (comp (ref "Q40")
      (value "AO3400A")
      (footprint "eagle-import:SOT23")
      (libsource (lib "eagle-import") (part "2N7002P"))
    )
    (comp (ref "Q41")
      (value "AO3401A")
      (footprint "eagle-import:SOT23")
      (libsource (lib "eagle-import") (part "AO3401A"))
    )
    (comp (ref "Q42")
      (value "AO3400A")
      (footprint "eagle-import:SOT23")
      (libsource (lib "eagle-import") (part "2N7002P"))
    )
    (comp (ref "Q43")
      (value "AO3401A")
      (footprint "eagle-import:SOT23")
      (libsource (lib "eagle-import") (part "AO3401A"))
    )
    (comp (ref "Q44")
      (value "AO3400A")
      (footprint "eagle-import:SOT23")
      (libsource (lib "eagle-import") (part "2N7002P"))
    )
    (comp (ref "Q45")
      (value "AO3401A")
      (footprint "eagle-import:SOT23")
      (libsource (lib "eagle-import") (part "AO3401A"))
    )
    (comp (ref "Q46")
      (value "AO3400A")
      (footprint "eagle-import:SOT23")
      (libsource (lib "eagle-import") (part "2N7002P"))
    )
    (comp (ref "Q47")
      (value "AO3401A")
      (footprint "eagle-import:SOT23")
      (libsource (lib "eagle-import") (part "AO3401A"))
    )
    (comp (ref "Q48")
      (value "AO3400A")
      (footprint "eagle-import:SOT23")
      (libsource (lib "eagle-import") (part "2N7002P"))
    )
    (comp (ref "R1")
      (value "10k")
      (footprint "eagle-import:R0402")
      (libsource (lib "eagle-import") (part "R-US_R0402"))
    )
    (comp (ref "R2")
      (value "10k")
      (footprint "eagle-import:R0402")
      (libsource (lib "eagle-import") (part "R-US_R0402"))
    )
    (comp (ref "R3")
      (value "8.2k")
      (footprint "eagle-import:R0402")
      (libsource (lib "eagle-import") (part "R-US_R0402"))
    )
    (comp (ref "R4")
      (value "10k")
      (footprint "eagle-import:R0402")
      (libsource (lib "eagle-import") (part "R-US_R0402"))
    )
    (comp (ref "R5")
      (value "10k")
      (footprint "eagle-import:R0402")
      (libsource (lib "eagle-import") (part "R-US_R0402"))
    )
    (comp (ref "R6")
      (value "10k")
      (footprint "eagle-import:R0402")
      (libsource (lib "eagle-import") (part "R-US_R0402"))
    )
    (comp (ref "R7")
      (value "100m")
      (footprint "eagle-import:R1206")
      (libsource (lib "eagle-import") (part "R-US_R1206"))
    )
    (comp (ref "R8")
      (value "100m")
      (footprint "eagle-import:R1206")
      (libsource (lib "eagle-import") (part "R-US_R1206"))
    )
    (comp (ref "R9")
      (value "10k")
      (footprint "eagle-import:R0402")
      (libsource (lib "eagle-import") (part "R-US_R0402"))
    )
    (comp (ref "R10")
      (value "1k")
      (footprint "eagle-import:R0402")
      (libsource (lib "eagle-import") (part "R-US_R0402"))
    )
    (comp (ref "R11")
      (value "1k")
      (footprint "eagle-import:R0402")
      (libsource (lib "eagle-import") (part "R-US_R0402"))
    )
    (comp (ref "R12")
      (value "10k")
      (footprint "eagle-import:R0402")
      (libsource (lib "eagle-import") (part "R-US_R0402"))
    )
    (comp (ref "R13")
      (value "20k")
      (footprint "eagle-import:R0402")
      (libsource (lib "eagle-import") (part "R-US_R0402"))
    )
    (comp (ref "R14")
      (value "20k")
      (footprint "eagle-import:R0402")
      (libsource (lib "eagle-import") (part "R-US_R0402"))
    )
    (comp (ref "R15")
      (value "10k")
      (footprint "eagle-import:R0402")
      (libsource (lib "eagle-import") (part "R-US_R0402"))
    )
    (comp (ref "R16")
      (value "10k")
      (footprint "eagle-import:R0402")
      (libsource (lib "eagle-import") (part "R-US_R0402"))
    )
    (comp (ref "R17")
      (value "10k")
      (footprint "eagle-import:R0402")
      (libsource (lib "eagle-import") (part "R-US_R0402"))
    )
    (comp (ref "R18")
      (value "120")
      (footprint "eagle-import:R0402")
      (libsource (lib "eagle-import") (part "R-US_R0402"))
    )
    (comp (ref "R19")
      (value "10k")
      (footprint "eagle-import:R0402")
      (libsource (lib "eagle-import") (part "R-US_R0402"))
    )
    (comp (ref "R20")
      (value "10k")
      (footprint "eagle-import:R0402")
      (libsource (lib "eagle-import") (part "R-US_R0402"))
    )
    (comp (ref "R21")
      (value "8.2k")
      (footprint "eagle-import:R0402")
      (libsource (lib "eagle-import") (part "R-US_R0402"))
    )
    (comp (ref "R22")
      (value "10k")
      (footprint "eagle-import:R0402")
      (libsource (lib "eagle-import") (part "R-US_R0402"))
    )
    (comp (ref "R23")
      (value "10k")
      (footprint "eagle-import:R0402")
      (libsource (lib "eagle-import") (part "R-US_R0402"))
    )
    (comp (ref "R24")
      (value "10k")
      (footprint "eagle-import:R0402")
      (libsource (lib "eagle-import") (part "R-US_R0402"))
    )
    (comp (ref "R25")
      (value "10k")
      (footprint "eagle-import:R0402")
      (libsource (lib "eagle-import") (part "R-US_R0402"))
    )
    (comp (ref "R26")
      (value "100m")
      (footprint "eagle-import:R1206")
      (libsource (lib "eagle-import") (part "R-US_R1206"))
    )
    (comp (ref "R27")
      (value "100m")
      (footprint "eagle-import:R1206")
      (libsource (lib "eagle-import") (part "R-US_R1206"))
    )
    (comp (ref "R28")
      (value "1k")
      (footprint "eagle-import:R0402")
      (libsource (lib "eagle-import") (part "R-US_R0402"))
    )
    (comp (ref "R29")
      (value "1k")
      (footprint "eagle-import:R0402")
      (libsource (lib "eagle-import") (part "R-US_R0402"))
    )
    (comp (ref "R30")
      (value "10k")
      (footprint "eagle-import:R0402")
      (libsource (lib "eagle-import") (part "R-US_R0402"))
    )
    (comp (ref "R31")
      (value "10k")
      (footprint "eagle-import:R0402")
      (libsource (lib "eagle-import") (part "R-US_R0402"))
    )
    (comp (ref "R32")
      (value "20k")
      (footprint "eagle-import:R0402")
      (libsource (lib "eagle-import") (part "R-US_R0402"))
    )
    (comp (ref "R33")
      (value "33k")
      (footprint "eagle-import:R0402")
      (libsource (lib "eagle-import") (part "R-US_R0402"))
    )
    (comp (ref "R34")
      (value "20k")
      (footprint "eagle-import:R0402")
      (libsource (lib "eagle-import") (part "R-US_R0402"))
    )
    (comp (ref "R35")
      (value "20k")
      (footprint "eagle-import:R0402")
      (libsource (lib "eagle-import") (part "R-US_R0402"))
    )
    (comp (ref "R36")
      (value "10k")
      (footprint "eagle-import:R0402")
      (libsource (lib "eagle-import") (part "R-US_R0402"))
    )
    (comp (ref "R37")
      (value "10k")
      (footprint "eagle-import:R0402")
      (libsource (lib "eagle-import") (part "R-US_R0402"))
    )
    (comp (ref "R38")
      (value "10k")
      (footprint "eagle-import:R0402")
      (libsource (lib "eagle-import") (part "R-US_R0402"))
    )
    (comp (ref "R39")
      (value "51k")
      (footprint "eagle-import:R0402")
      (libsource (lib "eagle-import") (part "R-US_R0402"))
    )
    (comp (ref "R40")
      (value "2.7k")
      (footprint "eagle-import:R0402")
      (libsource (lib "eagle-import") (part "R-US_R0402"))
    )
    (comp (ref "R41")
      (value "10k")
      (footprint "eagle-import:R0402")
      (libsource (lib "eagle-import") (part "R-US_R0402"))
    )
    (comp (ref "R42")
      (value "1.8k")
      (footprint "eagle-import:R0402")
      (libsource (lib "eagle-import") (part "R-US_R0402"))
    )
    (comp (ref "R43")
      (value "1k")
      (footprint "eagle-import:R0402")
      (libsource (lib "eagle-import") (part "R-US_R0402"))
    )
    (comp (ref "R44")
      (value "10k")
      (footprint "eagle-import:R0402")
      (libsource (lib "eagle-import") (part "R-US_R0402"))
    )
    (comp (ref "R45")
      (value "10k")
      (footprint "eagle-import:R0402")
      (libsource (lib "eagle-import") (part "R-US_R0402"))
    )
    (comp (ref "R46")
      (value "1k")
      (footprint "eagle-import:R0402")
      (libsource (lib "eagle-import") (part "R-US_R0402"))
    )
    (comp (ref "R47")
      (value "10k")
      (footprint "eagle-import:R0402")
      (libsource (lib "eagle-import") (part "R-US_R0402"))
    )
    (comp (ref "R48")
      (value "10k")
      (footprint "eagle-import:R0402")
      (libsource (lib "eagle-import") (part "R-US_R0402"))
    )
    (comp (ref "R49")
      (value "1k")
      (footprint "eagle-import:R0402")
      (libsource (lib "eagle-import") (part "R-US_R0402"))
    )
    (comp (ref "R50")
      (value "10k")
      (footprint "eagle-import:R0402")
      (libsource (lib "eagle-import") (part "R-US_R0402"))
    )
    (comp (ref "R51")
      (value "1k")
      (footprint "eagle-import:R0402")
      (libsource (lib "eagle-import") (part "R-US_R0402"))
    )
    (comp (ref "R52")
      (value "10k")
      (footprint "eagle-import:R0402")
      (libsource (lib "eagle-import") (part "R-US_R0402"))
    )
    (comp (ref "R53")
      (value "10k")
      (footprint "eagle-import:R0402")
      (libsource (lib "eagle-import") (part "R-US_R0402"))
    )
    (comp (ref "R54")
      (value "1k")
      (footprint "eagle-import:R0402")
      (libsource (lib "eagle-import") (part "R-US_R0402"))
    )
    (comp (ref "R55")
      (value "10k")
      (footprint "eagle-import:R0402")
      (libsource (lib "eagle-import") (part "R-US_R0402"))
    )
    (comp (ref "R56")
      (value "10k")
      (footprint "eagle-import:R0402")
      (libsource (lib "eagle-import") (part "R-US_R0402"))
    )
    (comp (ref "R57")
      (value "1k")
      (footprint "eagle-import:R0402")
      (libsource (lib "eagle-import") (part "R-US_R0402"))
    )
    (comp (ref "R58")
      (value "120")
      (footprint "eagle-import:R0402")
      (libsource (lib "eagle-import") (part "R-US_R0402"))
    )
    (comp (ref "R59")
      (value "10k")
      (footprint "eagle-import:R0402")
      (libsource (lib "eagle-import") (part "R-US_R0402"))
    )
    (comp (ref "R60")
      (value "1.8k")
      (footprint "eagle-import:R0402")
      (libsource (lib "eagle-import") (part "R-US_R0402"))
    )
    (comp (ref "R61")
      (value "100m")
      (footprint "eagle-import:R1206")
      (libsource (lib "eagle-import") (part "R-US_R1206"))
    )
    (comp (ref "R62")
      (value "1k")
      (footprint "eagle-import:R0402")
      (libsource (lib "eagle-import") (part "R-US_R0402"))
    )
    (comp (ref "R63")
      (value "10k")
      (footprint "eagle-import:R0402")
      (libsource (lib "eagle-import") (part "R-US_R0402"))
    )
    (comp (ref "R64")
      (value "8.2k")
      (footprint "eagle-import:R0402")
      (libsource (lib "eagle-import") (part "R-US_R0402"))
    )
    (comp (ref "R65")
      (value "10k")
      (footprint "eagle-import:R0402")
      (libsource (lib "eagle-import") (part "R-US_R0402"))
    )
    (comp (ref "R66")
      (value "51k")
      (footprint "eagle-import:R0402")
      (libsource (lib "eagle-import") (part "R-US_R0402"))
    )
    (comp (ref "R67")
      (value "2.7k")
      (footprint "eagle-import:R0402")
      (libsource (lib "eagle-import") (part "R-US_R0402"))
    )
    (comp (ref "R68")
      (value "20k")
      (footprint "eagle-import:R0402")
      (libsource (lib "eagle-import") (part "R-US_R0402"))
    )
    (comp (ref "R69")
      (value "1k")
      (footprint "eagle-import:R0402")
      (libsource (lib "eagle-import") (part "R-US_R0402"))
    )
    (comp (ref "R70")
      (value "20k")
      (footprint "eagle-import:R0402")
      (libsource (lib "eagle-import") (part "R-US_R0402"))
    )
    (comp (ref "R71")
      (value "1k")
      (footprint "eagle-import:R0402")
      (libsource (lib "eagle-import") (part "R-US_R0402"))
    )
    (comp (ref "R72")
      (value "20k")
      (footprint "eagle-import:R0402")
      (libsource (lib "eagle-import") (part "R-US_R0402"))
    )
    (comp (ref "R73")
      (value "100m")
      (footprint "eagle-import:R1206")
      (libsource (lib "eagle-import") (part "R-US_R1206"))
    )
    (comp (ref "R74")
      (value "1k")
      (footprint "eagle-import:R0402")
      (libsource (lib "eagle-import") (part "R-US_R0402"))
    )
    (comp (ref "R75")
      (value "1k")
      (footprint "eagle-import:R0402")
      (libsource (lib "eagle-import") (part "R-US_R0402"))
    )
    (comp (ref "R76")
      (value "1k")
      (footprint "eagle-import:R0402")
      (libsource (lib "eagle-import") (part "R-US_R0402"))
    )
    (comp (ref "R77")
      (value "1k")
      (footprint "eagle-import:R0402")
      (libsource (lib "eagle-import") (part "R-US_R0402"))
    )
    (comp (ref "R78")
      (value "1k")
      (footprint "eagle-import:R0402")
      (libsource (lib "eagle-import") (part "R-US_R0402"))
    )
    (comp (ref "R79")
      (value "10k")
      (footprint "eagle-import:R0402")
      (libsource (lib "eagle-import") (part "R-US_R0402"))
    )
    (comp (ref "R80")
      (value "10k")
      (footprint "eagle-import:R0402")
      (libsource (lib "eagle-import") (part "R-US_R0402"))
    )
    (comp (ref "R81")
      (value "10k")
      (footprint "eagle-import:R0402")
      (libsource (lib "eagle-import") (part "R-US_R0402"))
    )
    (comp (ref "R82")
      (value "10k")
      (footprint "eagle-import:R0402")
      (libsource (lib "eagle-import") (part "R-US_R0402"))
    )
    (comp (ref "R83")
      (value "10k")
      (footprint "eagle-import:R0402")
      (libsource (lib "eagle-import") (part "R-US_R0402"))
    )
    (comp (ref "R84")
      (value "10k")
      (footprint "eagle-import:R0402")
      (libsource (lib "eagle-import") (part "R-US_R0402"))
    )
    (comp (ref "R85")
      (value "10k")
      (footprint "eagle-import:R0402")
      (libsource (lib "eagle-import") (part "R-US_R0402"))
    )
    (comp (ref "R86")
      (value "100m")
      (footprint "eagle-import:R1206")
      (libsource (lib "eagle-import") (part "R-US_R1206"))
    )
    (comp (ref "R87")
      (value "10k")
      (footprint "eagle-import:R0402")
      (libsource (lib "eagle-import") (part "R-US_R0402"))
    )
    (comp (ref "R88")
      (value "8.2k")
      (footprint "eagle-import:R0402")
      (libsource (lib "eagle-import") (part "R-US_R0402"))
    )
    (comp (ref "R89")
      (value "10k")
      (footprint "eagle-import:R0402")
      (libsource (lib "eagle-import") (part "R-US_R0402"))
    )
    (comp (ref "R90")
      (value "1k")
      (footprint "eagle-import:R0402")
      (libsource (lib "eagle-import") (part "R-US_R0402"))
    )
    (comp (ref "R91")
      (value "20k")
      (footprint "eagle-import:R0402")
      (libsource (lib "eagle-import") (part "R-US_R0402"))
    )
    (comp (ref "R92")
      (value "1k")
      (footprint "eagle-import:R0402")
      (libsource (lib "eagle-import") (part "R-US_R0402"))
    )
    (comp (ref "R93")
      (value "20k")
      (footprint "eagle-import:R0402")
      (libsource (lib "eagle-import") (part "R-US_R0402"))
    )
    (comp (ref "R94")
      (value "100m")
      (footprint "eagle-import:R1206")
      (libsource (lib "eagle-import") (part "R-US_R1206"))
    )
    (comp (ref "R95")
      (value "10k")
      (footprint "eagle-import:R0402")
      (libsource (lib "eagle-import") (part "R-US_R0402"))
    )
    (comp (ref "R96")
      (value "10k")
      (footprint "eagle-import:R0402")
      (libsource (lib "eagle-import") (part "R-US_R0402"))
    )
    (comp (ref "R97")
      (value "10k")
      (footprint "eagle-import:R0402")
      (libsource (lib "eagle-import") (part "R-US_R0402"))
    )
    (comp (ref "R98")
      (value "10k")
      (footprint "eagle-import:R0402")
      (libsource (lib "eagle-import") (part "R-US_R0402"))
    )
    (comp (ref "R99")
      (value "10k")
      (footprint "eagle-import:R0402")
      (libsource (lib "eagle-import") (part "R-US_R0402"))
    )
    (comp (ref "R100")
      (value "10k")
      (footprint "eagle-import:R0402")
      (libsource (lib "eagle-import") (part "R-US_R0402"))
    )
    (comp (ref "R101")
      (value "10k")
      (footprint "eagle-import:R0402")
      (libsource (lib "eagle-import") (part "R-US_R0402"))
    )
    (comp (ref "R102")
      (value "10k")
      (footprint "eagle-import:R0402")
      (libsource (lib "eagle-import") (part "R-US_R0402"))
    )
    (comp (ref "R103")
      (value "10k")
      (footprint "eagle-import:R0402")
      (libsource (lib "eagle-import") (part "R-US_R0402"))
    )
    (comp (ref "R104")
      (value "10k")
      (footprint "eagle-import:R0402")
      (libsource (lib "eagle-import") (part "R-US_R0402"))
    )
    (comp (ref "R105")
      (value "10k")
      (footprint "eagle-import:R0402")
      (libsource (lib "eagle-import") (part "R-US_R0402"))
    )
    (comp (ref "R106")
      (value "10k")
      (footprint "eagle-import:R0402")
      (libsource (lib "eagle-import") (part "R-US_R0402"))
    )
    (comp (ref "R107")
      (value "10k")
      (footprint "eagle-import:R0402")
      (libsource (lib "eagle-import") (part "R-US_R0402"))
    )
    (comp (ref "R108")
      (value "10k")
      (footprint "eagle-import:R0402")
      (libsource (lib "eagle-import") (part "R-US_R0402"))
    )
    (comp (ref "R109")
      (value "10k")
      (footprint "eagle-import:R0402")
      (libsource (lib "eagle-import") (part "R-US_R0402"))
    )
    (comp (ref "R110")
      (value "10k")
      (footprint "eagle-import:R0402")
      (libsource (lib "eagle-import") (part "R-US_R0402"))
    )
    (comp (ref "R111")
      (value "10k")
      (footprint "eagle-import:R0402")
      (libsource (lib "eagle-import") (part "R-US_R0402"))
    )
    (comp (ref "R112")
      (value "10k")
      (footprint "eagle-import:R0402")
      (libsource (lib "eagle-import") (part "R-US_R0402"))
    )
    (comp (ref "R113")
      (value "33k")
      (footprint "eagle-import:R0402")
      (libsource (lib "eagle-import") (part "R-US_R0402"))
    )
    (comp (ref "R114")
      (value "10k")
      (footprint "eagle-import:R0402")
      (libsource (lib "eagle-import") (part "R-US_R0402"))
    )
    (comp (ref "U1")
      (value "MCP6002SOIC")
      (footprint "eagle-import:8-SOIC")
      (libsource (lib "eagle-import") (part "MCP6002SOIC"))
    )
    (comp (ref "U2")
      (value "CJ431")
      (footprint "eagle-import:SOT23")
      (libsource (lib "eagle-import") (part "TL431SOT23"))
    )
    (comp (ref "U3")
      (value "3.3V")
      (footprint "eagle-import:SOT-89")
      (libsource (lib "eagle-import") (part "AP1117UR133-B"))
    )
    (comp (ref "U4")
      (value "FP6291")
      (footprint "eagle-import:SOT23-6")
      (libsource (lib "eagle-import") (part "FP6291"))
    )
    (comp (ref "U5")
      (value "STM32_BLUE_PILL")
      (footprint "eagle-import:STM32_BLUE_PILL_USABLE")
      (libsource (lib "eagle-import") (part "STM32_BLUE_PILL"))
    )
    (comp (ref "U6")
      (value "CJ431")
      (footprint "eagle-import:SOT23")
      (libsource (lib "eagle-import") (part "TL431SOT23"))
    )
    (comp (ref "U7")
      (value "STM32_BLUE_PILL")
      (footprint "eagle-import:STM32_BLUE_PILL_USABLE")
      (libsource (lib "eagle-import") (part "STM32_BLUE_PILL"))
    )
    (comp (ref "U8")
      (value "3.3V")
      (footprint "eagle-import:SOT-89")
      (libsource (lib "eagle-import") (part "AP1117UR133-B"))
    )
    (comp (ref "U9")
      (value "FP6291")
      (footprint "eagle-import:SOT23-6")
      (libsource (lib "eagle-import") (part "FP6291"))
    )
    (comp (ref "U10")
      (value "MCP6002SOIC")
      (footprint "eagle-import:8-SOIC")
      (libsource (lib "eagle-import") (part "MCP6002SOIC"))
    )
  )
  (nets
    (net (code "1") (name "2V1") (class "Default")
      (node (ref "C22") (pin "1") (pinfunction "1_1") (pintype "passive"))
      (node (ref "R58") (pin "2") (pinfunction "2_2") (pintype "passive"))
      (node (ref "R59") (pin "2") (pinfunction "2_2") (pintype "passive"))
      (node (ref "R85") (pin "2") (pinfunction "2_2") (pintype "passive"))
      (node (ref "U6") (pin "1") (pinfunction "K_1") (pintype "passive"))
      (node (ref "U6") (pin "2") (pinfunction "REF_2") (pintype "passive"))
      (node (ref "U7") (pin "A5") (pinfunction "A5_A5") (pintype "bidirectional"))
    )
    (net (code "2") (name "2V495") (class "Default")
      (node (ref "C19") (pin "1") (pinfunction "1_1") (pintype "passive"))
      (node (ref "R18") (pin "2") (pinfunction "2_2") (pintype "passive"))
      (node (ref "R30") (pin "2") (pinfunction "2_2") (pintype "passive"))
      (node (ref "R9") (pin "2") (pinfunction "2_2") (pintype "passive"))
      (node (ref "U2") (pin "1") (pinfunction "K_1") (pintype "passive"))
      (node (ref "U2") (pin "2") (pinfunction "REF_2") (pintype "passive"))
      (node (ref "U5") (pin "A5") (pinfunction "A5_A5") (pintype "bidirectional"))
    )
    (net (code "3") (name "3V1") (class "Default")
      (node (ref "C21") (pin "1") (pinfunction "1_1") (pintype "passive"))
      (node (ref "C24") (pin "1") (pinfunction "1_1") (pintype "passive"))
      (node (ref "JP38") (pin "3") (pinfunction "3_3") (pintype "passive"))
      (node (ref "JP40") (pin "3") (pinfunction "3_3") (pintype "passive"))
      (node (ref "JP42") (pin "3") (pinfunction "3_3") (pintype "passive"))
      (node (ref "JP44") (pin "3") (pinfunction "3_3") (pintype "passive"))
      (node (ref "JP46") (pin "3") (pinfunction "3_3") (pintype "passive"))
      (node (ref "JP48") (pin "3") (pinfunction "3_3") (pintype "passive"))
      (node (ref "JP65") (pin "2") (pinfunction "2_2") (pintype "passive"))
      (node (ref "R60") (pin "1") (pinfunction "1_1") (pintype "passive"))
      (node (ref "U7") (pin "3V3") (pinfunction "3V3_3V3") (pintype "bidirectional"))
      (node (ref "U7") (pin "3V3_2") (pinfunction "3V3_2_3V3_2") (pintype "bidirectional"))
      (node (ref "U8") (pin "1") (pinfunction "VO_1") (pintype "bidirectional"))
    )
    (net (code "4") (name "3V3") (class "Default")
      (node (ref "C17") (pin "1") (pinfunction "1_1") (pintype "passive"))
      (node (ref "C18") (pin "1") (pinfunction "1_1") (pintype "passive"))
      (node (ref "JP18") (pin "3") (pinfunction "3_3") (pintype "passive"))
      (node (ref "JP21") (pin "3") (pinfunction "3_3") (pintype "passive"))
      (node (ref "JP24") (pin "3") (pinfunction "3_3") (pintype "passive"))
      (node (ref "JP28") (pin "2") (pinfunction "2_2") (pintype "passive"))
      (node (ref "JP30") (pin "3") (pinfunction "3_3") (pintype "passive"))
      (node (ref "JP33") (pin "3") (pinfunction "3_3") (pintype "passive"))
      (node (ref "JP36") (pin "3") (pinfunction "3_3") (pintype "passive"))
      (node (ref "R42") (pin "1") (pinfunction "1_1") (pintype "passive"))
      (node (ref "U3") (pin "1") (pinfunction "VO_1") (pintype "bidirectional"))
      (node (ref "U5") (pin "3V3") (pinfunction "3V3_3V3") (pintype "bidirectional"))
      (node (ref "U5") (pin "3V3_2") (pinfunction "3V3_2_3V3_2") (pintype "bidirectional"))
    )
    (net (code "5") (name "12V") (class "Default")
      (node (ref "C12") (pin "1") (pinfunction "1_1") (pintype "passive"))
      (node (ref "C13") (pin "1") (pinfunction "1_1") (pintype "passive"))
      (node (ref "C15") (pin "1") (pinfunction "1_1") (pintype "passive"))
      (node (ref "D11") (pin "K") (pinfunction "CATHODE_K") (pintype "passive"))
      (node (ref "JP1") (pin "3") (pinfunction "3_3") (pintype "passive"))
      (node (ref "JP10") (pin "3") (pinfunction "3_3") (pintype "passive"))
      (node (ref "JP13") (pin "3") (pinfunction "3_3") (pintype "passive"))
      (node (ref "JP17") (pin "3") (pinfunction "3_3") (pintype "passive"))
      (node (ref "JP28") (pin "4") (pinfunction "4_4") (pintype "passive"))
      (node (ref "JP29") (pin "3") (pinfunction "3_3") (pintype "passive"))
      (node (ref "JP4") (pin "3") (pinfunction "3_3") (pintype "passive"))
      (node (ref "JP7") (pin "3") (pinfunction "3_3") (pintype "passive"))
      (node (ref "Q1") (pin "2") (pinfunction "S_2") (pintype "bidirectional"))
      (node (ref "Q11") (pin "2") (pinfunction "S_2") (pintype "bidirectional"))
      (node (ref "Q13") (pin "2") (pinfunction "S_2") (pintype "bidirectional"))
      (node (ref "Q16") (pin "2") (pinfunction "S_2") (pintype "bidirectional"))
      (node (ref "Q21") (pin "2") (pinfunction "S_2") (pintype "bidirectional"))
      (node (ref "Q5") (pin "2") (pinfunction "S_2") (pintype "bidirectional"))
      (node (ref "Q7") (pin "2") (pinfunction "S_2") (pintype "bidirectional"))
      (node (ref "R15") (pin "1") (pinfunction "1_1") (pintype "passive"))
      (node (ref "R19") (pin "1") (pinfunction "1_1") (pintype "passive"))
      (node (ref "R25") (pin "1") (pinfunction "1_1") (pintype "passive"))
      (node (ref "R33") (pin "2") (pinfunction "2_2") (pintype "passive"))
      (node (ref "R38") (pin "1") (pinfunction "1_1") (pintype "passive"))
      (node (ref "R39") (pin "2") (pinfunction "2_2") (pintype "passive"))
      (node (ref "R47") (pin "1") (pinfunction "1_1") (pintype "passive"))
      (node (ref "R5") (pin "1") (pinfunction "1_1") (pintype "passive"))
      (node (ref "R55") (pin "1") (pinfunction "1_1") (pintype "passive"))
    )
    (net (code "6") (name "12V1") (class "Default")
      (node (ref "C28") (pin "1") (pinfunction "1_1") (pintype "passive"))
      (node (ref "C31") (pin "1") (pinfunction "1_1") (pintype "passive"))
      (node (ref "C32") (pin "1") (pinfunction "1_1") (pintype "passive"))
      (node (ref "D21") (pin "K") (pinfunction "CATHODE_K") (pintype "passive"))
      (node (ref "JP65") (pin "4") (pinfunction "4_4") (pintype "passive"))
      (node (ref "JP66") (pin "3") (pinfunction "3_3") (pintype "passive"))
      (node (ref "JP67") (pin "3") (pinfunction "3_3") (pintype "passive"))
      (node (ref "JP68") (pin "3") (pinfunction "3_3") (pintype "passive"))
      (node (ref "JP69") (pin "3") (pinfunction "3_3") (pintype "passive"))
      (node (ref "JP70") (pin "3") (pinfunction "3_3") (pintype "passive"))
      (node (ref "JP71") (pin "3") (pinfunction "3_3") (pintype "passive"))
      (node (ref "JP72") (pin "3") (pinfunction "3_3") (pintype "passive"))
      (node (ref "Q33") (pin "2") (pinfunction "S_2") (pintype "bidirectional"))
      (node (ref "Q37") (pin "2") (pinfunction "S_2") (pintype "bidirectional"))
      (node (ref "Q39") (pin "2") (pinfunction "S_2") (pintype "bidirectional"))
      (node (ref "Q41") (pin "2") (pinfunction "S_2") (pintype "bidirectional"))
      (node (ref "Q43") (pin "2") (pinfunction "S_2") (pintype "bidirectional"))
      (node (ref "Q45") (pin "2") (pinfunction "S_2") (pintype "bidirectional"))
      (node (ref "Q47") (pin "2") (pinfunction "S_2") (pintype "bidirectional"))
      (node (ref "R100") (pin "1") (pinfunction "1_1") (pintype "passive"))
      (node (ref "R102") (pin "1") (pinfunction "1_1") (pintype "passive"))
      (node (ref "R104") (pin "1") (pinfunction "1_1") (pintype "passive"))
      (node (ref "R106") (pin "1") (pinfunction "1_1") (pintype "passive"))
      (node (ref "R108") (pin "1") (pinfunction "1_1") (pintype "passive"))
      (node (ref "R110") (pin "1") (pinfunction "1_1") (pintype "passive"))
      (node (ref "R113") (pin "2") (pinfunction "2_2") (pintype "passive"))
      (node (ref "R66") (pin "2") (pinfunction "2_2") (pintype "passive"))
      (node (ref "R98") (pin "1") (pinfunction "1_1") (pintype "passive"))
    )
    (net (code "7") (name "12VSNS") (class "Default")
      (node (ref "C10") (pin "1") (pinfunction "1_1") (pintype "passive"))
      (node (ref "R31") (pin "2") (pinfunction "2_2") (pintype "passive"))
      (node (ref "R33") (pin "1") (pinfunction "1_1") (pintype "passive"))
      (node (ref "U5") (pin "A4") (pinfunction "A4_A4") (pintype "bidirectional"))
    )
    (net (code "8") (name "12VSNS1") (class "Default")
      (node (ref "C38") (pin "1") (pinfunction "1_1") (pintype "passive"))
      (node (ref "R113") (pin "1") (pinfunction "1_1") (pintype "passive"))
      (node (ref "R114") (pin "2") (pinfunction "2_2") (pintype "passive"))
      (node (ref "U7") (pin "A4") (pinfunction "A4_A4") (pintype "bidirectional"))
    )
    (net (code "9") (name "AUXADC1") (class "Default")
      (node (ref "JP26") (pin "3") (pinfunction "3_3") (pintype "passive"))
      (node (ref "U5") (pin "A1") (pinfunction "A1_A1") (pintype "bidirectional"))
    )
    (net (code "10") (name "AUXADC2") (class "Default")
      (node (ref "JP26") (pin "2") (pinfunction "2_2") (pintype "passive"))
      (node (ref "U5") (pin "A0") (pinfunction "A0_A0") (pintype "bidirectional"))
    )
    (net (code "11") (name "AUXADC3") (class "Default")
      (node (ref "JP63") (pin "3") (pinfunction "3_3") (pintype "passive"))
      (node (ref "U7") (pin "A1") (pinfunction "A1_A1") (pintype "bidirectional"))
    )
    (net (code "12") (name "AUXADC4") (class "Default")
      (node (ref "JP63") (pin "2") (pinfunction "2_2") (pintype "passive"))
      (node (ref "U7") (pin "A0") (pinfunction "A0_A0") (pintype "bidirectional"))
    )
    (net (code "13") (name "AUXI1") (class "Default")
      (node (ref "JP63") (pin "1") (pinfunction "1_1") (pintype "passive"))
      (node (ref "U7") (pin "C13") (pinfunction "C13_C13") (pintype "bidirectional"))
    )
    (net (code "14") (name "AUXI3") (class "Default")
      (node (ref "JP26") (pin "1") (pinfunction "1_1") (pintype "passive"))
      (node (ref "U5") (pin "C13") (pinfunction "C13_C13") (pintype "bidirectional"))
    )
    (net (code "15") (name "AUXIO1") (class "Default")
      (node (ref "JP25") (pin "2") (pinfunction "2_2") (pintype "passive"))
      (node (ref "U5") (pin "B8") (pinfunction "B8_B8") (pintype "bidirectional"))
    )
    (net (code "16") (name "AUXIO2") (class "Default")
      (node (ref "JP25") (pin "1") (pinfunction "1_1") (pintype "passive"))
      (node (ref "U5") (pin "B9") (pinfunction "B9_B9") (pintype "bidirectional"))
    )
    (net (code "17") (name "AUXIO3") (class "Default")
      (node (ref "JP64") (pin "1") (pinfunction "1_1") (pintype "passive"))
      (node (ref "U7") (pin "B9") (pinfunction "B9_B9") (pintype "bidirectional"))
    )
    (net (code "18") (name "AUXIO4") (class "Default")
      (node (ref "JP64") (pin "2") (pinfunction "2_2") (pintype "passive"))
      (node (ref "U7") (pin "B8") (pinfunction "B8_B8") (pintype "bidirectional"))
    )
    (net (code "19") (name "D+2P0") (class "Default")
      (node (ref "CON1") (pin "3-D+") (pinfunction "D+_3-D+") (pintype "bidirectional"))
      (node (ref "CON2") (pin "3-D+") (pinfunction "D+_3-D+") (pintype "bidirectional"))
    )
    (net (code "20") (name "D+2P1") (class "Default")
      (node (ref "CON5") (pin "3-D+") (pinfunction "D+_3-D+") (pintype "bidirectional"))
      (node (ref "CON6") (pin "3-D+") (pinfunction "D+_3-D+") (pintype "bidirectional"))
    )
    (net (code "21") (name "D+3P0") (class "Default")
      (node (ref "CON3") (pin "3-D+") (pinfunction "D+_3-D+") (pintype "bidirectional"))
      (node (ref "CON4") (pin "3-D+") (pinfunction "D+_3-D+") (pintype "bidirectional"))
    )
    (net (code "22") (name "D+3P1") (class "Default")
      (node (ref "CON7") (pin "3-D+") (pinfunction "D+_3-D+") (pintype "bidirectional"))
      (node (ref "CON8") (pin "3-D+") (pinfunction "D+_3-D+") (pintype "bidirectional"))
    )
    (net (code "23") (name "D-2P0") (class "Default")
      (node (ref "CON1") (pin "2-D-") (pinfunction "D-_2-D-") (pintype "bidirectional"))
      (node (ref "CON2") (pin "2-D-") (pinfunction "D-_2-D-") (pintype "bidirectional"))
    )
    (net (code "24") (name "D-2P1") (class "Default")
      (node (ref "CON5") (pin "2-D-") (pinfunction "D-_2-D-") (pintype "bidirectional"))
      (node (ref "CON6") (pin "2-D-") (pinfunction "D-_2-D-") (pintype "bidirectional"))
    )
    (net (code "25") (name "D-3P0") (class "Default")
      (node (ref "CON3") (pin "2-D-") (pinfunction "D-_2-D-") (pintype "bidirectional"))
      (node (ref "CON4") (pin "2-D-") (pinfunction "D-_2-D-") (pintype "bidirectional"))
    )
    (net (code "26") (name "D-3P1") (class "Default")
      (node (ref "CON7") (pin "2-D-") (pinfunction "D-_2-D-") (pintype "bidirectional"))
      (node (ref "CON8") (pin "2-D-") (pinfunction "D-_2-D-") (pintype "bidirectional"))
    )
    (net (code "27") (name "GND") (class "Default")
      (node (ref "C1") (pin "2") (pinfunction "2_2") (pintype "passive"))
      (node (ref "C10") (pin "2") (pinfunction "2_2") (pintype "passive"))
      (node (ref "C11") (pin "2") (pinfunction "2_2") (pintype "passive"))
      (node (ref "C12") (pin "2") (pinfunction "2_2") (pintype "passive"))
      (node (ref "C13") (pin "2") (pinfunction "2_2") (pintype "passive"))
      (node (ref "C14") (pin "2") (pinfunction "2_2") (pintype "passive"))
      (node (ref "C15") (pin "2") (pinfunction "2_2") (pintype "passive"))
      (node (ref "C16") (pin "2") (pinfunction "2_2") (pintype "passive"))
      (node (ref "C17") (pin "2") (pinfunction "2_2") (pintype "passive"))
      (node (ref "C18") (pin "2") (pinfunction "2_2") (pintype "passive"))
      (node (ref "C19") (pin "2") (pinfunction "2_2") (pintype "passive"))
      (node (ref "C2") (pin "2") (pinfunction "2_2") (pintype "passive"))
      (node (ref "C3") (pin "2") (pinfunction "2_2") (pintype "passive"))
      (node (ref "C4") (pin "2") (pinfunction "2_2") (pintype "passive"))
      (node (ref "C5") (pin "2") (pinfunction "2_2") (pintype "passive"))
      (node (ref "C6") (pin "2") (pinfunction "2_2") (pintype "passive"))
      (node (ref "C7") (pin "2") (pinfunction "2_2") (pintype "passive"))
      (node (ref "C8") (pin "2") (pinfunction "2_2") (pintype "passive"))
      (node (ref "C9") (pin "2") (pinfunction "2_2") (pintype "passive"))
      (node (ref "CON1") (pin "4-GND") (pinfunction "GND_4-GND") (pintype "bidirectional"))
      (node (ref "CON2") (pin "5-GND") (pinfunction "GND_5-GND") (pintype "bidirectional"))
      (node (ref "CON3") (pin "4-GND") (pinfunction "GND_4-GND") (pintype "bidirectional"))
      (node (ref "CON3") (pin "7-GND") (pinfunction "GND_D_7-GND") (pintype "bidirectional"))
      (node (ref "CON4") (pin "4-GND") (pinfunction "GND_4-GND") (pintype "bidirectional"))
      (node (ref "CON4") (pin "7-GNDD") (pinfunction "GND_D_7-GNDD") (pintype "bidirectional"))
      (node (ref "J1") (pin "1") (pinfunction "1_1") (pintype "passive"))
      (node (ref "J2") (pin "1") (pinfunction "1_1") (pintype "passive"))
      (node (ref "JP12") (pin "1") (pinfunction "1_1") (pintype "passive"))
      (node (ref "JP15") (pin "1") (pinfunction "1_1") (pintype "passive"))
      (node (ref "JP16") (pin "1") (pinfunction "1_1") (pintype "passive"))
      (node (ref "JP20") (pin "1") (pinfunction "1_1") (pintype "passive"))
      (node (ref "JP22") (pin "1") (pinfunction "1_1") (pintype "passive"))
      (node (ref "JP23") (pin "1") (pinfunction "1_1") (pintype "passive"))
      (node (ref "JP27") (pin "1") (pinfunction "1_1") (pintype "passive"))
      (node (ref "JP28") (pin "1") (pinfunction "1_1") (pintype "passive"))
      (node (ref "JP3") (pin "1") (pinfunction "1_1") (pintype "passive"))
      (node (ref "JP32") (pin "1") (pinfunction "1_1") (pintype "passive"))
      (node (ref "JP34") (pin "1") (pinfunction "1_1") (pintype "passive"))
      (node (ref "JP35") (pin "1") (pinfunction "1_1") (pintype "passive"))
      (node (ref "JP6") (pin "1") (pinfunction "1_1") (pintype "passive"))
      (node (ref "JP9") (pin "1") (pinfunction "1_1") (pintype "passive"))
      (node (ref "Q10") (pin "2") (pinfunction "S_2") (pintype "bidirectional"))
      (node (ref "Q12") (pin "2") (pinfunction "S_2") (pintype "bidirectional"))
      (node (ref "Q14") (pin "2") (pinfunction "S_2") (pintype "bidirectional"))
      (node (ref "Q15") (pin "2") (pinfunction "S_2") (pintype "bidirectional"))
      (node (ref "Q17") (pin "2") (pinfunction "S_2") (pintype "bidirectional"))
      (node (ref "Q18") (pin "2") (pinfunction "S_2") (pintype "bidirectional"))
      (node (ref "Q19") (pin "2") (pinfunction "S_2") (pintype "bidirectional"))
      (node (ref "Q2") (pin "2") (pinfunction "S_2") (pintype "bidirectional"))
      (node (ref "Q20") (pin "2") (pinfunction "S_2") (pintype "bidirectional"))
      (node (ref "Q22") (pin "2") (pinfunction "S_2") (pintype "bidirectional"))
      (node (ref "Q23") (pin "2") (pinfunction "S_2") (pintype "bidirectional"))
      (node (ref "Q24") (pin "2") (pinfunction "S_2") (pintype "bidirectional"))
      (node (ref "Q4") (pin "2") (pinfunction "S_2") (pintype "bidirectional"))
      (node (ref "Q6") (pin "2") (pinfunction "S_2") (pintype "bidirectional"))
      (node (ref "Q8") (pin "2") (pinfunction "S_2") (pintype "bidirectional"))
      (node (ref "R1") (pin "2") (pinfunction "2_2") (pintype "passive"))
      (node (ref "R12") (pin "1") (pinfunction "1_1") (pintype "passive"))
      (node (ref "R13") (pin "2") (pinfunction "2_2") (pintype "passive"))
      (node (ref "R17") (pin "1") (pinfunction "1_1") (pintype "passive"))
      (node (ref "R2") (pin "1") (pinfunction "1_1") (pintype "passive"))
      (node (ref "R20") (pin "2") (pinfunction "2_2") (pintype "passive"))
      (node (ref "R22") (pin "1") (pinfunction "1_1") (pintype "passive"))
      (node (ref "R23") (pin "1") (pinfunction "1_1") (pintype "passive"))
      (node (ref "R31") (pin "1") (pinfunction "1_1") (pintype "passive"))
      (node (ref "R32") (pin "2") (pinfunction "2_2") (pintype "passive"))
      (node (ref "R35") (pin "1") (pinfunction "1_1") (pintype "passive"))
      (node (ref "R36") (pin "1") (pinfunction "1_1") (pintype "passive"))
      (node (ref "R4") (pin "1") (pinfunction "1_1") (pintype "passive"))
      (node (ref "R40") (pin "1") (pinfunction "1_1") (pintype "passive"))
      (node (ref "R41") (pin "1") (pinfunction "1_1") (pintype "passive"))
      (node (ref "R44") (pin "1") (pinfunction "1_1") (pintype "passive"))
      (node (ref "R45") (pin "1") (pinfunction "1_1") (pintype "passive"))
      (node (ref "R48") (pin "1") (pinfunction "1_1") (pintype "passive"))
      (node (ref "R50") (pin "1") (pinfunction "1_1") (pintype "passive"))
      (node (ref "R52") (pin "1") (pinfunction "1_1") (pintype "passive"))
      (node (ref "R53") (pin "1") (pinfunction "1_1") (pintype "passive"))
      (node (ref "R56") (pin "1") (pinfunction "1_1") (pintype "passive"))
      (node (ref "U1") (pin "4") (pinfunction "GND_4") (pintype "power_in"))
      (node (ref "U2") (pin "3") (pinfunction "A_3") (pintype "passive"))
      (node (ref "U3") (pin "2") (pinfunction "GND_2") (pintype "bidirectional"))
      (node (ref "U3") (pin "2@1") (pinfunction "GND_2@1") (pintype "bidirectional"))
      (node (ref "U4") (pin "2") (pinfunction "GND_2") (pintype "bidirectional"))
      (node (ref "U5") (pin "GND") (pinfunction "GND_GND") (pintype "bidirectional"))
      (node (ref "U5") (pin "GND2") (pinfunction "GND2_GND2") (pintype "bidirectional"))
      (node (ref "U5") (pin "GND4") (pinfunction "GND4_GND4") (pintype "bidirectional"))
    )
    (net (code "28") (name "GND1") (class "Default")
      (node (ref "C20") (pin "2") (pinfunction "2_2") (pintype "passive"))
      (node (ref "C21") (pin "2") (pinfunction "2_2") (pintype "passive"))
      (node (ref "C22") (pin "2") (pinfunction "2_2") (pintype "passive"))
      (node (ref "C23") (pin "2") (pinfunction "2_2") (pintype "passive"))
      (node (ref "C24") (pin "2") (pinfunction "2_2") (pintype "passive"))
      (node (ref "C25") (pin "2") (pinfunction "2_2") (pintype "passive"))
      (node (ref "C26") (pin "2") (pinfunction "2_2") (pintype "passive"))
      (node (ref "C27") (pin "2") (pinfunction "2_2") (pintype "passive"))
      (node (ref "C28") (pin "2") (pinfunction "2_2") (pintype "passive"))
      (node (ref "C29") (pin "2") (pinfunction "2_2") (pintype "passive"))
      (node (ref "C30") (pin "2") (pinfunction "2_2") (pintype "passive"))
      (node (ref "C31") (pin "2") (pinfunction "2_2") (pintype "passive"))
      (node (ref "C32") (pin "2") (pinfunction "2_2") (pintype "passive"))
      (node (ref "C33") (pin "2") (pinfunction "2_2") (pintype "passive"))
      (node (ref "C34") (pin "2") (pinfunction "2_2") (pintype "passive"))
      (node (ref "C35") (pin "2") (pinfunction "2_2") (pintype "passive"))
      (node (ref "C36") (pin "2") (pinfunction "2_2") (pintype "passive"))
      (node (ref "C37") (pin "2") (pinfunction "2_2") (pintype "passive"))
      (node (ref "C38") (pin "2") (pinfunction "2_2") (pintype "passive"))
      (node (ref "CON5") (pin "5-GND") (pinfunction "GND_5-GND") (pintype "bidirectional"))
      (node (ref "CON6") (pin "4-GND") (pinfunction "GND_4-GND") (pintype "bidirectional"))
      (node (ref "CON7") (pin "4-GND") (pinfunction "GND_4-GND") (pintype "bidirectional"))
      (node (ref "CON7") (pin "7-GNDD") (pinfunction "GND_D_7-GNDD") (pintype "bidirectional"))
      (node (ref "CON8") (pin "4-GND") (pinfunction "GND_4-GND") (pintype "bidirectional"))
      (node (ref "CON8") (pin "7-GND") (pinfunction "GND_D_7-GND") (pintype "bidirectional"))
      (node (ref "J3") (pin "1") (pinfunction "1_1") (pintype "passive"))
      (node (ref "J4") (pin "1") (pinfunction "1_1") (pintype "passive"))
      (node (ref "JP37") (pin "1") (pinfunction "1_1") (pintype "passive"))
      (node (ref "JP39") (pin "1") (pinfunction "1_1") (pintype "passive"))
      (node (ref "JP41") (pin "1") (pinfunction "1_1") (pintype "passive"))
      (node (ref "JP43") (pin "1") (pinfunction "1_1") (pintype "passive"))
      (node (ref "JP45") (pin "1") (pinfunction "1_1") (pintype "passive"))
      (node (ref "JP47") (pin "1") (pinfunction "1_1") (pintype "passive"))
      (node (ref "JP50") (pin "1") (pinfunction "1_1") (pintype "passive"))
      (node (ref "JP52") (pin "1") (pinfunction "1_1") (pintype "passive"))
      (node (ref "JP54") (pin "1") (pinfunction "1_1") (pintype "passive"))
      (node (ref "JP56") (pin "1") (pinfunction "1_1") (pintype "passive"))
      (node (ref "JP58") (pin "1") (pinfunction "1_1") (pintype "passive"))
      (node (ref "JP60") (pin "1") (pinfunction "1_1") (pintype "passive"))
      (node (ref "JP62") (pin "1") (pinfunction "1_1") (pintype "passive"))
      (node (ref "JP65") (pin "1") (pinfunction "1_1") (pintype "passive"))
      (node (ref "Q25") (pin "2") (pinfunction "S_2") (pintype "bidirectional"))
      (node (ref "Q27") (pin "2") (pinfunction "S_2") (pintype "bidirectional"))
      (node (ref "Q28") (pin "2") (pinfunction "S_2") (pintype "bidirectional"))
      (node (ref "Q29") (pin "2") (pinfunction "S_2") (pintype "bidirectional"))
      (node (ref "Q30") (pin "2") (pinfunction "S_2") (pintype "bidirectional"))
      (node (ref "Q31") (pin "2") (pinfunction "S_2") (pintype "bidirectional"))
      (node (ref "Q32") (pin "2") (pinfunction "S_2") (pintype "bidirectional"))
      (node (ref "Q35") (pin "2") (pinfunction "S_2") (pintype "bidirectional"))
      (node (ref "Q36") (pin "2") (pinfunction "S_2") (pintype "bidirectional"))
      (node (ref "Q38") (pin "2") (pinfunction "S_2") (pintype "bidirectional"))
      (node (ref "Q40") (pin "2") (pinfunction "S_2") (pintype "bidirectional"))
      (node (ref "Q42") (pin "2") (pinfunction "S_2") (pintype "bidirectional"))
      (node (ref "Q44") (pin "2") (pinfunction "S_2") (pintype "bidirectional"))
      (node (ref "Q46") (pin "2") (pinfunction "S_2") (pintype "bidirectional"))
      (node (ref "Q48") (pin "2") (pinfunction "S_2") (pintype "bidirectional"))
      (node (ref "R101") (pin "1") (pinfunction "1_1") (pintype "passive"))
      (node (ref "R103") (pin "1") (pinfunction "1_1") (pintype "passive"))
      (node (ref "R105") (pin "1") (pinfunction "1_1") (pintype "passive"))
      (node (ref "R107") (pin "1") (pinfunction "1_1") (pintype "passive"))
      (node (ref "R109") (pin "1") (pinfunction "1_1") (pintype "passive"))
      (node (ref "R111") (pin "2") (pinfunction "2_2") (pintype "passive"))
      (node (ref "R112") (pin "2") (pinfunction "2_2") (pintype "passive"))
      (node (ref "R114") (pin "1") (pinfunction "1_1") (pintype "passive"))
      (node (ref "R65") (pin "1") (pinfunction "1_1") (pintype "passive"))
      (node (ref "R67") (pin "1") (pinfunction "1_1") (pintype "passive"))
      (node (ref "R68") (pin "1") (pinfunction "1_1") (pintype "passive"))
      (node (ref "R70") (pin "2") (pinfunction "2_2") (pintype "passive"))
      (node (ref "R79") (pin "1") (pinfunction "1_1") (pintype "passive"))
      (node (ref "R80") (pin "1") (pinfunction "1_1") (pintype "passive"))
      (node (ref "R81") (pin "1") (pinfunction "1_1") (pintype "passive"))
      (node (ref "R82") (pin "1") (pinfunction "1_1") (pintype "passive"))
      (node (ref "R83") (pin "1") (pinfunction "1_1") (pintype "passive"))
      (node (ref "R84") (pin "1") (pinfunction "1_1") (pintype "passive"))
      (node (ref "R89") (pin "1") (pinfunction "1_1") (pintype "passive"))
      (node (ref "R91") (pin "2") (pinfunction "2_2") (pintype "passive"))
      (node (ref "R97") (pin "1") (pinfunction "1_1") (pintype "passive"))
      (node (ref "R99") (pin "1") (pinfunction "1_1") (pintype "passive"))
      (node (ref "U10") (pin "4") (pinfunction "GND_4") (pintype "power_in"))
      (node (ref "U6") (pin "3") (pinfunction "A_3") (pintype "passive"))
      (node (ref "U7") (pin "GND") (pinfunction "GND_GND") (pintype "bidirectional"))
      (node (ref "U7") (pin "GND2") (pinfunction "GND2_GND2") (pintype "bidirectional"))
      (node (ref "U7") (pin "GND4") (pinfunction "GND4_GND4") (pintype "bidirectional"))
      (node (ref "U8") (pin "2") (pinfunction "GND_2") (pintype "bidirectional"))
      (node (ref "U8") (pin "2@1") (pinfunction "GND_2@1") (pintype "bidirectional"))
      (node (ref "U9") (pin "2") (pinfunction "GND_2") (pintype "bidirectional"))
    )
    (net (code "29") (name "Net-(D1-ANODE)") (class "Default")
      (node (ref "D1") (pin "A") (pinfunction "ANODE_A") (pintype "passive"))
      (node (ref "JP2") (pin "2") (pinfunction "2_2") (pintype "passive"))
      (node (ref "JP3") (pin "2") (pinfunction "2_2") (pintype "passive"))
    )
    (net (code "30") (name "Net-(D1-CATHODE)") (class "Default")
      (node (ref "D1") (pin "K") (pinfunction "CATHODE_K") (pintype "passive"))
      (node (ref "JP1") (pin "2") (pinfunction "2_2") (pintype "passive"))
      (node (ref "JP2") (pin "1") (pinfunction "1_1") (pintype "passive"))
    )
    (net (code "31") (name "Net-(D5-ANODE)") (class "Default")
      (node (ref "D5") (pin "A") (pinfunction "ANODE_A") (pintype "passive"))
      (node (ref "JP5") (pin "2") (pinfunction "2_2") (pintype "passive"))
      (node (ref "JP6") (pin "2") (pinfunction "2_2") (pintype "passive"))
    )
    (net (code "32") (name "Net-(D5-CATHODE)") (class "Default")
      (node (ref "D5") (pin "K") (pinfunction "CATHODE_K") (pintype "passive"))
      (node (ref "JP4") (pin "2") (pinfunction "2_2") (pintype "passive"))
      (node (ref "JP5") (pin "1") (pinfunction "1_1") (pintype "passive"))
    )
    (net (code "33") (name "Net-(D6-ANODE)") (class "Default")
      (node (ref "D6") (pin "A") (pinfunction "ANODE_A") (pintype "passive"))
      (node (ref "JP8") (pin "2") (pinfunction "2_2") (pintype "passive"))
      (node (ref "JP9") (pin "2") (pinfunction "2_2") (pintype "passive"))
    )
    (net (code "34") (name "Net-(D6-CATHODE)") (class "Default")
      (node (ref "D6") (pin "K") (pinfunction "CATHODE_K") (pintype "passive"))
      (node (ref "JP7") (pin "2") (pinfunction "2_2") (pintype "passive"))
      (node (ref "JP8") (pin "1") (pinfunction "1_1") (pintype "passive"))
    )
    (net (code "35") (name "Net-(D7-CATHODE)") (class "Default")
      (node (ref "C7") (pin "1") (pinfunction "1_1") (pintype "passive"))
      (node (ref "C8") (pin "1") (pinfunction "1_1") (pintype "passive"))
      (node (ref "C9") (pin "1") (pinfunction "1_1") (pintype "passive"))
      (node (ref "D7") (pin "K") (pinfunction "CATHODE_K") (pintype "passive"))
      (node (ref "D8") (pin "K") (pinfunction "CATHODE_K") (pintype "passive"))
      (node (ref "D9") (pin "K") (pinfunction "CATHODE_K") (pintype "passive"))
      (node (ref "L1") (pin "1") (pinfunction "P$1_1") (pintype "passive"))
      (node (ref "U4") (pin "4") (pinfunction "EN_4") (pintype "bidirectional"))
      (node (ref "U4") (pin "5") (pinfunction "VCC_5") (pintype "bidirectional"))
    )
    (net (code "36") (name "Net-(D10-ANODE)") (class "Default")
      (node (ref "D10") (pin "A") (pinfunction "ANODE_A") (pintype "passive"))
      (node (ref "JP11") (pin "2") (pinfunction "2_2") (pintype "passive"))
      (node (ref "JP12") (pin "2") (pinfunction "2_2") (pintype "passive"))
    )
    (net (code "37") (name "Net-(D10-CATHODE)") (class "Default")
      (node (ref "D10") (pin "K") (pinfunction "CATHODE_K") (pintype "passive"))
      (node (ref "JP10") (pin "2") (pinfunction "2_2") (pintype "passive"))
      (node (ref "JP11") (pin "1") (pinfunction "1_1") (pintype "passive"))
    )
    (net (code "38") (name "Net-(D11-ANODE)") (class "Default")
      (node (ref "D11") (pin "A") (pinfunction "ANODE_A") (pintype "passive"))
      (node (ref "L1") (pin "2") (pinfunction "P$2_2") (pintype "passive"))
      (node (ref "U4") (pin "1") (pinfunction "LX_1") (pintype "bidirectional"))
    )
    (net (code "39") (name "Net-(D12-ANODE)") (class "Default")
      (node (ref "D12") (pin "A") (pinfunction "ANODE_A") (pintype "passive"))
      (node (ref "JP14") (pin "2") (pinfunction "2_2") (pintype "passive"))
      (node (ref "JP15") (pin "2") (pinfunction "2_2") (pintype "passive"))
    )
    (net (code "40") (name "Net-(D12-CATHODE)") (class "Default")
      (node (ref "D12") (pin "K") (pinfunction "CATHODE_K") (pintype "passive"))
      (node (ref "JP13") (pin "2") (pinfunction "2_2") (pintype "passive"))
      (node (ref "JP14") (pin "1") (pinfunction "1_1") (pintype "passive"))
    )
    (net (code "41") (name "Net-(D13-ANODE)") (class "Default")
      (node (ref "D13") (pin "A") (pinfunction "ANODE_A") (pintype "passive"))
      (node (ref "JP19") (pin "2") (pinfunction "2_2") (pintype "passive"))
      (node (ref "JP22") (pin "2") (pinfunction "2_2") (pintype "passive"))
    )
    (net (code "42") (name "Net-(D13-CATHODE)") (class "Default")
      (node (ref "D13") (pin "K") (pinfunction "CATHODE_K") (pintype "passive"))
      (node (ref "JP17") (pin "2") (pinfunction "2_2") (pintype "passive"))
      (node (ref "JP19") (pin "1") (pinfunction "1_1") (pintype "passive"))
    )
    (net (code "43") (name "Net-(D14-ANODE)") (class "Default")
      (node (ref "D14") (pin "A") (pinfunction "ANODE_A") (pintype "passive"))
      (node (ref "JP31") (pin "2") (pinfunction "2_2") (pintype "passive"))
      (node (ref "JP34") (pin "2") (pinfunction "2_2") (pintype "passive"))
    )
    (net (code "44") (name "Net-(D14-CATHODE)") (class "Default")
      (node (ref "D14") (pin "K") (pinfunction "CATHODE_K") (pintype "passive"))
      (node (ref "JP29") (pin "2") (pinfunction "2_2") (pintype "passive"))
      (node (ref "JP31") (pin "1") (pinfunction "1_1") (pintype "passive"))
    )
    (net (code "45") (name "Net-(D18-CATHODE)") (class "Default")
      (node (ref "C27") (pin "1") (pinfunction "1_1") (pintype "passive"))
      (node (ref "C29") (pin "1") (pinfunction "1_1") (pintype "passive"))
      (node (ref "C30") (pin "1") (pinfunction "1_1") (pintype "passive"))
      (node (ref "D18") (pin "K") (pinfunction "CATHODE_K") (pintype "passive"))
      (node (ref "D19") (pin "K") (pinfunction "CATHODE_K") (pintype "passive"))
      (node (ref "D20") (pin "K") (pinfunction "CATHODE_K") (pintype "passive"))
      (node (ref "L2") (pin "1") (pinfunction "P$1_1") (pintype "passive"))
      (node (ref "U9") (pin "4") (pinfunction "EN_4") (pintype "bidirectional"))
      (node (ref "U9") (pin "5") (pinfunction "VCC_5") (pintype "bidirectional"))
    )
    (net (code "46") (name "Net-(D21-ANODE)") (class "Default")
      (node (ref "D21") (pin "A") (pinfunction "ANODE_A") (pintype "passive"))
      (node (ref "L2") (pin "2") (pinfunction "P$2_2") (pintype "passive"))
      (node (ref "U9") (pin "1") (pinfunction "LX_1") (pintype "bidirectional"))
    )
    (net (code "47") (name "Net-(D22-ANODE)") (class "Default")
      (node (ref "D22") (pin "A") (pinfunction "ANODE_A") (pintype "passive"))
      (node (ref "JP49") (pin "2") (pinfunction "2_2") (pintype "passive"))
      (node (ref "JP50") (pin "2") (pinfunction "2_2") (pintype "passive"))
    )
    (net (code "48") (name "Net-(D22-CATHODE)") (class "Default")
      (node (ref "D22") (pin "K") (pinfunction "CATHODE_K") (pintype "passive"))
      (node (ref "JP49") (pin "1") (pinfunction "1_1") (pintype "passive"))
      (node (ref "JP66") (pin "2") (pinfunction "2_2") (pintype "passive"))
    )
    (net (code "49") (name "Net-(D23-ANODE)") (class "Default")
      (node (ref "D23") (pin "A") (pinfunction "ANODE_A") (pintype "passive"))
      (node (ref "JP51") (pin "2") (pinfunction "2_2") (pintype "passive"))
      (node (ref "JP52") (pin "2") (pinfunction "2_2") (pintype "passive"))
    )
    (net (code "50") (name "Net-(D23-CATHODE)") (class "Default")
      (node (ref "D23") (pin "K") (pinfunction "CATHODE_K") (pintype "passive"))
      (node (ref "JP51") (pin "1") (pinfunction "1_1") (pintype "passive"))
      (node (ref "JP67") (pin "2") (pinfunction "2_2") (pintype "passive"))
    )
    (net (code "51") (name "Net-(D24-ANODE)") (class "Default")
      (node (ref "D24") (pin "A") (pinfunction "ANODE_A") (pintype "passive"))
      (node (ref "JP53") (pin "2") (pinfunction "2_2") (pintype "passive"))
      (node (ref "JP54") (pin "2") (pinfunction "2_2") (pintype "passive"))
    )
    (net (code "52") (name "Net-(D24-CATHODE)") (class "Default")
      (node (ref "D24") (pin "K") (pinfunction "CATHODE_K") (pintype "passive"))
      (node (ref "JP53") (pin "1") (pinfunction "1_1") (pintype "passive"))
      (node (ref "JP68") (pin "2") (pinfunction "2_2") (pintype "passive"))
    )
    (net (code "53") (name "Net-(D25-ANODE)") (class "Default")
      (node (ref "D25") (pin "A") (pinfunction "ANODE_A") (pintype "passive"))
      (node (ref "JP55") (pin "2") (pinfunction "2_2") (pintype "passive"))
      (node (ref "JP56") (pin "2") (pinfunction "2_2") (pintype "passive"))
    )
    (net (code "54") (name "Net-(D25-CATHODE)") (class "Default")
      (node (ref "D25") (pin "K") (pinfunction "CATHODE_K") (pintype "passive"))
      (node (ref "JP55") (pin "1") (pinfunction "1_1") (pintype "passive"))
      (node (ref "JP69") (pin "2") (pinfunction "2_2") (pintype "passive"))
    )
    (net (code "55") (name "Net-(D26-ANODE)") (class "Default")
      (node (ref "D26") (pin "A") (pinfunction "ANODE_A") (pintype "passive"))
      (node (ref "JP57") (pin "2") (pinfunction "2_2") (pintype "passive"))
      (node (ref "JP58") (pin "2") (pinfunction "2_2") (pintype "passive"))
    )
    (net (code "56") (name "Net-(D26-CATHODE)") (class "Default")
      (node (ref "D26") (pin "K") (pinfunction "CATHODE_K") (pintype "passive"))
      (node (ref "JP57") (pin "1") (pinfunction "1_1") (pintype "passive"))
      (node (ref "JP70") (pin "2") (pinfunction "2_2") (pintype "passive"))
    )
    (net (code "57") (name "Net-(D27-ANODE)") (class "Default")
      (node (ref "D27") (pin "A") (pinfunction "ANODE_A") (pintype "passive"))
      (node (ref "JP59") (pin "2") (pinfunction "2_2") (pintype "passive"))
      (node (ref "JP60") (pin "2") (pinfunction "2_2") (pintype "passive"))
    )
    (net (code "58") (name "Net-(D27-CATHODE)") (class "Default")
      (node (ref "D27") (pin "K") (pinfunction "CATHODE_K") (pintype "passive"))
      (node (ref "JP59") (pin "1") (pinfunction "1_1") (pintype "passive"))
      (node (ref "JP71") (pin "2") (pinfunction "2_2") (pintype "passive"))
    )
    (net (code "59") (name "Net-(D28-ANODE)") (class "Default")
      (node (ref "D28") (pin "A") (pinfunction "ANODE_A") (pintype "passive"))
      (node (ref "JP61") (pin "2") (pinfunction "2_2") (pintype "passive"))
      (node (ref "JP62") (pin "2") (pinfunction "2_2") (pintype "passive"))
    )
    (net (code "60") (name "Net-(D28-CATHODE)") (class "Default")
      (node (ref "D28") (pin "K") (pinfunction "CATHODE_K") (pintype "passive"))
      (node (ref "JP61") (pin "1") (pinfunction "1_1") (pintype "passive"))
      (node (ref "JP72") (pin "2") (pinfunction "2_2") (pintype "passive"))
    )
    (net (code "61") (name "Net-(JP18-Pad2)") (class "Default")
      (node (ref "JP18") (pin "2") (pinfunction "2_2") (pintype "passive"))
      (node (ref "R43") (pin "2") (pinfunction "2_2") (pintype "passive"))
    )
    (net (code "62") (name "Net-(JP21-Pad2)") (class "Default")
      (node (ref "JP21") (pin "2") (pinfunction "2_2") (pintype "passive"))
      (node (ref "R46") (pin "2") (pinfunction "2_2") (pintype "passive"))
    )
    (net (code "63") (name "Net-(JP24-Pad2)") (class "Default")
      (node (ref "JP24") (pin "2") (pinfunction "2_2") (pintype "passive"))
      (node (ref "R49") (pin "2") (pinfunction "2_2") (pintype "passive"))
    )
    (net (code "64") (name "Net-(JP30-Pad2)") (class "Default")
      (node (ref "JP30") (pin "2") (pinfunction "2_2") (pintype "passive"))
      (node (ref "R51") (pin "2") (pinfunction "2_2") (pintype "passive"))
    )
    (net (code "65") (name "Net-(JP33-Pad2)") (class "Default")
      (node (ref "JP33") (pin "2") (pinfunction "2_2") (pintype "passive"))
      (node (ref "R54") (pin "2") (pinfunction "2_2") (pintype "passive"))
    )
    (net (code "66") (name "Net-(JP36-Pad2)") (class "Default")
      (node (ref "JP36") (pin "2") (pinfunction "2_2") (pintype "passive"))
      (node (ref "R57") (pin "2") (pinfunction "2_2") (pintype "passive"))
    )
    (net (code "67") (name "Net-(JP38-Pad2)") (class "Default")
      (node (ref "JP38") (pin "2") (pinfunction "2_2") (pintype "passive"))
      (node (ref "R62") (pin "2") (pinfunction "2_2") (pintype "passive"))
    )
    (net (code "68") (name "Net-(JP40-Pad2)") (class "Default")
      (node (ref "JP40") (pin "2") (pinfunction "2_2") (pintype "passive"))
      (node (ref "R74") (pin "2") (pinfunction "2_2") (pintype "passive"))
    )
    (net (code "69") (name "Net-(JP42-Pad2)") (class "Default")
      (node (ref "JP42") (pin "2") (pinfunction "2_2") (pintype "passive"))
      (node (ref "R75") (pin "2") (pinfunction "2_2") (pintype "passive"))
    )
    (net (code "70") (name "Net-(JP44-Pad2)") (class "Default")
      (node (ref "JP44") (pin "2") (pinfunction "2_2") (pintype "passive"))
      (node (ref "R76") (pin "2") (pinfunction "2_2") (pintype "passive"))
    )
    (net (code "71") (name "Net-(JP46-Pad2)") (class "Default")
      (node (ref "JP46") (pin "2") (pinfunction "2_2") (pintype "passive"))
      (node (ref "R77") (pin "2") (pinfunction "2_2") (pintype "passive"))
    )
    (net (code "72") (name "Net-(JP48-Pad2)") (class "Default")
      (node (ref "JP48") (pin "2") (pinfunction "2_2") (pintype "passive"))
      (node (ref "R78") (pin "2") (pinfunction "2_2") (pintype "passive"))
    )
    (net (code "73") (name "Net-(Q1-D)") (class "Default")
      (node (ref "JP1") (pin "1") (pinfunction "1_1") (pintype "passive"))
      (node (ref "Q1") (pin "3") (pinfunction "D_3") (pintype "bidirectional"))
    )
    (net (code "74") (name "Net-(Q1-G)") (class "Default")
      (node (ref "JP3") (pin "3") (pinfunction "3_3") (pintype "passive"))
      (node (ref "Q1") (pin "1") (pinfunction "G_1") (pintype "bidirectional"))
      (node (ref "Q2") (pin "3") (pinfunction "D_3") (pintype "bidirectional"))
      (node (ref "R5") (pin "2") (pinfunction "2_2") (pintype "passive"))
    )
    (net (code "75") (name "Net-(Q3-G)") (class "Default")
      (node (ref "Q3") (pin "4") (pinfunction "G_4") (pintype "bidirectional"))
      (node (ref "Q4") (pin "3") (pinfunction "D_3") (pintype "bidirectional"))
      (node (ref "R6") (pin "1") (pinfunction "1_1") (pintype "passive"))
    )
    (net (code "76") (name "Net-(Q3-S-Pad1)") (class "Default")
      (node (ref "Q3") (pin "1") (pinfunction "S_1") (pintype "bidirectional"))
      (node (ref "Q3") (pin "2") (pinfunction "S_2") (pintype "bidirectional"))
      (node (ref "Q3") (pin "3") (pinfunction "S_3") (pintype "bidirectional"))
      (node (ref "R10") (pin "2") (pinfunction "2_2") (pintype "passive"))
      (node (ref "R6") (pin "2") (pinfunction "2_2") (pintype "passive"))
      (node (ref "R7") (pin "1") (pinfunction "1_1") (pintype "passive"))
      (node (ref "R8") (pin "1") (pinfunction "1_1") (pintype "passive"))
    )
    (net (code "77") (name "Net-(Q5-D)") (class "Default")
      (node (ref "JP4") (pin "1") (pinfunction "1_1") (pintype "passive"))
      (node (ref "Q5") (pin "3") (pinfunction "D_3") (pintype "bidirectional"))
    )
    (net (code "78") (name "Net-(Q5-G)") (class "Default")
      (node (ref "JP6") (pin "3") (pinfunction "3_3") (pintype "passive"))
      (node (ref "Q5") (pin "1") (pinfunction "G_1") (pintype "bidirectional"))
      (node (ref "Q6") (pin "3") (pinfunction "D_3") (pintype "bidirectional"))
      (node (ref "R15") (pin "2") (pinfunction "2_2") (pintype "passive"))
    )
    (net (code "79") (name "Net-(Q7-D)") (class "Default")
      (node (ref "JP7") (pin "1") (pinfunction "1_1") (pintype "passive"))
      (node (ref "Q7") (pin "3") (pinfunction "D_3") (pintype "bidirectional"))
    )
    (net (code "80") (name "Net-(Q7-G)") (class "Default")
      (node (ref "JP9") (pin "3") (pinfunction "3_3") (pintype "passive"))
      (node (ref "Q7") (pin "1") (pinfunction "G_1") (pintype "bidirectional"))
      (node (ref "Q8") (pin "3") (pinfunction "D_3") (pintype "bidirectional"))
      (node (ref "R19") (pin "2") (pinfunction "2_2") (pintype "passive"))
    )
    (net (code "81") (name "Net-(Q9-S-Pad1)") (class "Default")
      (node (ref "Q9") (pin "1") (pinfunction "S_1") (pintype "bidirectional"))
      (node (ref "Q9") (pin "2") (pinfunction "S_2") (pintype "bidirectional"))
      (node (ref "Q9") (pin "3") (pinfunction "S_3") (pintype "bidirectional"))
      (node (ref "R24") (pin "2") (pinfunction "2_2") (pintype "passive"))
      (node (ref "R26") (pin "1") (pinfunction "1_1") (pintype "passive"))
      (node (ref "R27") (pin "1") (pinfunction "1_1") (pintype "passive"))
      (node (ref "R28") (pin "2") (pinfunction "2_2") (pintype "passive"))
    )
    (net (code "82") (name "Net-(Q10-D)") (class "Default")
      (node (ref "Q10") (pin "3") (pinfunction "D_3") (pintype "bidirectional"))
      (node (ref "Q9") (pin "4") (pinfunction "G_4") (pintype "bidirectional"))
      (node (ref "R24") (pin "1") (pinfunction "1_1") (pintype "passive"))
    )
    (net (code "83") (name "Net-(Q11-D)") (class "Default")
      (node (ref "JP10") (pin "1") (pinfunction "1_1") (pintype "passive"))
      (node (ref "Q11") (pin "3") (pinfunction "D_3") (pintype "bidirectional"))
    )
    (net (code "84") (name "Net-(Q11-G)") (class "Default")
      (node (ref "JP12") (pin "3") (pinfunction "3_3") (pintype "passive"))
      (node (ref "Q11") (pin "1") (pinfunction "G_1") (pintype "bidirectional"))
      (node (ref "Q12") (pin "3") (pinfunction "D_3") (pintype "bidirectional"))
      (node (ref "R25") (pin "2") (pinfunction "2_2") (pintype "passive"))
    )
    (net (code "85") (name "Net-(Q13-D)") (class "Default")
      (node (ref "JP13") (pin "1") (pinfunction "1_1") (pintype "passive"))
      (node (ref "Q13") (pin "3") (pinfunction "D_3") (pintype "bidirectional"))
    )
    (net (code "86") (name "Net-(Q13-G)") (class "Default")
      (node (ref "JP15") (pin "3") (pinfunction "3_3") (pintype "passive"))
      (node (ref "Q13") (pin "1") (pinfunction "G_1") (pintype "bidirectional"))
      (node (ref "Q14") (pin "3") (pinfunction "D_3") (pintype "bidirectional"))
      (node (ref "R38") (pin "2") (pinfunction "2_2") (pintype "passive"))
    )
    (net (code "87") (name "Net-(Q15-D)") (class "Default")
      (node (ref "JP16") (pin "2") (pinfunction "2_2") (pintype "passive"))
      (node (ref "Q15") (pin "3") (pinfunction "D_3") (pintype "bidirectional"))
      (node (ref "R43") (pin "1") (pinfunction "1_1") (pintype "passive"))
    )
    (net (code "88") (name "Net-(Q16-D)") (class "Default")
      (node (ref "JP17") (pin "1") (pinfunction "1_1") (pintype "passive"))
      (node (ref "Q16") (pin "3") (pinfunction "D_3") (pintype "bidirectional"))
    )
    (net (code "89") (name "Net-(Q16-G)") (class "Default")
      (node (ref "JP22") (pin "3") (pinfunction "3_3") (pintype "passive"))
      (node (ref "Q16") (pin "1") (pinfunction "G_1") (pintype "bidirectional"))
      (node (ref "Q18") (pin "3") (pinfunction "D_3") (pintype "bidirectional"))
      (node (ref "R47") (pin "2") (pinfunction "2_2") (pintype "passive"))
    )
    (net (code "90") (name "Net-(Q17-D)") (class "Default")
      (node (ref "JP20") (pin "2") (pinfunction "2_2") (pintype "passive"))
      (node (ref "Q17") (pin "3") (pinfunction "D_3") (pintype "bidirectional"))
      (node (ref "R46") (pin "1") (pinfunction "1_1") (pintype "passive"))
    )
    (net (code "91") (name "Net-(Q19-D)") (class "Default")
      (node (ref "JP23") (pin "2") (pinfunction "2_2") (pintype "passive"))
      (node (ref "Q19") (pin "3") (pinfunction "D_3") (pintype "bidirectional"))
      (node (ref "R49") (pin "1") (pinfunction "1_1") (pintype "passive"))
    )
    (net (code "92") (name "Net-(Q20-D)") (class "Default")
      (node (ref "JP27") (pin "2") (pinfunction "2_2") (pintype "passive"))
      (node (ref "Q20") (pin "3") (pinfunction "D_3") (pintype "bidirectional"))
      (node (ref "R51") (pin "1") (pinfunction "1_1") (pintype "passive"))
    )
    (net (code "93") (name "Net-(Q21-D)") (class "Default")
      (node (ref "JP29") (pin "1") (pinfunction "1_1") (pintype "passive"))
      (node (ref "Q21") (pin "3") (pinfunction "D_3") (pintype "bidirectional"))
    )
    (net (code "94") (name "Net-(Q21-G)") (class "Default")
      (node (ref "JP34") (pin "3") (pinfunction "3_3") (pintype "passive"))
      (node (ref "Q21") (pin "1") (pinfunction "G_1") (pintype "bidirectional"))
      (node (ref "Q23") (pin "3") (pinfunction "D_3") (pintype "bidirectional"))
      (node (ref "R55") (pin "2") (pinfunction "2_2") (pintype "passive"))
    )
    (net (code "95") (name "Net-(Q22-D)") (class "Default")
      (node (ref "JP32") (pin "2") (pinfunction "2_2") (pintype "passive"))
      (node (ref "Q22") (pin "3") (pinfunction "D_3") (pintype "bidirectional"))
      (node (ref "R54") (pin "1") (pinfunction "1_1") (pintype "passive"))
    )
    (net (code "96") (name "Net-(Q24-D)") (class "Default")
      (node (ref "JP35") (pin "2") (pinfunction "2_2") (pintype "passive"))
      (node (ref "Q24") (pin "3") (pinfunction "D_3") (pintype "bidirectional"))
      (node (ref "R57") (pin "1") (pinfunction "1_1") (pintype "passive"))
    )
    (net (code "97") (name "Net-(Q25-D)") (class "Default")
      (node (ref "JP37") (pin "2") (pinfunction "2_2") (pintype "passive"))
      (node (ref "Q25") (pin "3") (pinfunction "D_3") (pintype "bidirectional"))
      (node (ref "R62") (pin "1") (pinfunction "1_1") (pintype "passive"))
    )
    (net (code "98") (name "Net-(Q26-G)") (class "Default")
      (node (ref "Q26") (pin "4") (pinfunction "G_4") (pintype "bidirectional"))
      (node (ref "Q27") (pin "3") (pinfunction "D_3") (pintype "bidirectional"))
      (node (ref "R63") (pin "1") (pinfunction "1_1") (pintype "passive"))
    )
    (net (code "99") (name "Net-(Q26-S-Pad1)") (class "Default")
      (node (ref "Q26") (pin "1") (pinfunction "S_1") (pintype "bidirectional"))
      (node (ref "Q26") (pin "2") (pinfunction "S_2") (pintype "bidirectional"))
      (node (ref "Q26") (pin "3") (pinfunction "S_3") (pintype "bidirectional"))
      (node (ref "R61") (pin "1") (pinfunction "1_1") (pintype "passive"))
      (node (ref "R63") (pin "2") (pinfunction "2_2") (pintype "passive"))
      (node (ref "R71") (pin "2") (pinfunction "2_2") (pintype "passive"))
      (node (ref "R73") (pin "1") (pinfunction "1_1") (pintype "passive"))
    )
    (net (code "100") (name "Net-(Q28-D)") (class "Default")
      (node (ref "JP39") (pin "2") (pinfunction "2_2") (pintype "passive"))
      (node (ref "Q28") (pin "3") (pinfunction "D_3") (pintype "bidirectional"))
      (node (ref "R74") (pin "1") (pinfunction "1_1") (pintype "passive"))
    )
    (net (code "101") (name "Net-(Q29-D)") (class "Default")
      (node (ref "JP41") (pin "2") (pinfunction "2_2") (pintype "passive"))
      (node (ref "Q29") (pin "3") (pinfunction "D_3") (pintype "bidirectional"))
      (node (ref "R75") (pin "1") (pinfunction "1_1") (pintype "passive"))
    )
    (net (code "102") (name "Net-(Q30-D)") (class "Default")
      (node (ref "JP43") (pin "2") (pinfunction "2_2") (pintype "passive"))
      (node (ref "Q30") (pin "3") (pinfunction "D_3") (pintype "bidirectional"))
      (node (ref "R76") (pin "1") (pinfunction "1_1") (pintype "passive"))
    )
    (net (code "103") (name "Net-(Q31-D)") (class "Default")
      (node (ref "JP45") (pin "2") (pinfunction "2_2") (pintype "passive"))
      (node (ref "Q31") (pin "3") (pinfunction "D_3") (pintype "bidirectional"))
      (node (ref "R77") (pin "1") (pinfunction "1_1") (pintype "passive"))
    )
    (net (code "104") (name "Net-(Q32-D)") (class "Default")
      (node (ref "JP47") (pin "2") (pinfunction "2_2") (pintype "passive"))
      (node (ref "Q32") (pin "3") (pinfunction "D_3") (pintype "bidirectional"))
      (node (ref "R78") (pin "1") (pinfunction "1_1") (pintype "passive"))
    )
    (net (code "105") (name "Net-(Q33-D)") (class "Default")
      (node (ref "JP66") (pin "1") (pinfunction "1_1") (pintype "passive"))
      (node (ref "Q33") (pin "3") (pinfunction "D_3") (pintype "bidirectional"))
    )
    (net (code "106") (name "Net-(Q33-G)") (class "Default")
      (node (ref "JP50") (pin "3") (pinfunction "3_3") (pintype "passive"))
      (node (ref "Q33") (pin "1") (pinfunction "G_1") (pintype "bidirectional"))
      (node (ref "Q36") (pin "3") (pinfunction "D_3") (pintype "bidirectional"))
      (node (ref "R98") (pin "2") (pinfunction "2_2") (pintype "passive"))
    )
    (net (code "107") (name "Net-(Q34-G)") (class "Default")
      (node (ref "Q34") (pin "4") (pinfunction "G_4") (pintype "bidirectional"))
      (node (ref "Q35") (pin "3") (pinfunction "D_3") (pintype "bidirectional"))
      (node (ref "R87") (pin "1") (pinfunction "1_1") (pintype "passive"))
    )
    (net (code "108") (name "Net-(Q34-S-Pad1)") (class "Default")
      (node (ref "Q34") (pin "1") (pinfunction "S_1") (pintype "bidirectional"))
      (node (ref "Q34") (pin "2") (pinfunction "S_2") (pintype "bidirectional"))
      (node (ref "Q34") (pin "3") (pinfunction "S_3") (pintype "bidirectional"))
      (node (ref "R86") (pin "1") (pinfunction "1_1") (pintype "passive"))
      (node (ref "R87") (pin "2") (pinfunction "2_2") (pintype "passive"))
      (node (ref "R92") (pin "2") (pinfunction "2_2") (pintype "passive"))
      (node (ref "R94") (pin "1") (pinfunction "1_1") (pintype "passive"))
    )
    (net (code "109") (name "Net-(Q37-D)") (class "Default")
      (node (ref "JP67") (pin "1") (pinfunction "1_1") (pintype "passive"))
      (node (ref "Q37") (pin "3") (pinfunction "D_3") (pintype "bidirectional"))
    )
    (net (code "110") (name "Net-(Q37-G)") (class "Default")
      (node (ref "JP52") (pin "3") (pinfunction "3_3") (pintype "passive"))
      (node (ref "Q37") (pin "1") (pinfunction "G_1") (pintype "bidirectional"))
      (node (ref "Q38") (pin "3") (pinfunction "D_3") (pintype "bidirectional"))
      (node (ref "R100") (pin "2") (pinfunction "2_2") (pintype "passive"))
    )
    (net (code "111") (name "Net-(Q39-D)") (class "Default")
      (node (ref "JP68") (pin "1") (pinfunction "1_1") (pintype "passive"))
      (node (ref "Q39") (pin "3") (pinfunction "D_3") (pintype "bidirectional"))
    )
    (net (code "112") (name "Net-(Q39-G)") (class "Default")
      (node (ref "JP54") (pin "3") (pinfunction "3_3") (pintype "passive"))
      (node (ref "Q39") (pin "1") (pinfunction "G_1") (pintype "bidirectional"))
      (node (ref "Q40") (pin "3") (pinfunction "D_3") (pintype "bidirectional"))
      (node (ref "R102") (pin "2") (pinfunction "2_2") (pintype "passive"))
    )
    (net (code "113") (name "Net-(Q41-D)") (class "Default")
      (node (ref "JP69") (pin "1") (pinfunction "1_1") (pintype "passive"))
      (node (ref "Q41") (pin "3") (pinfunction "D_3") (pintype "bidirectional"))
    )
    (net (code "114") (name "Net-(Q41-G)") (class "Default")
      (node (ref "JP56") (pin "3") (pinfunction "3_3") (pintype "passive"))
      (node (ref "Q41") (pin "1") (pinfunction "G_1") (pintype "bidirectional"))
      (node (ref "Q42") (pin "3") (pinfunction "D_3") (pintype "bidirectional"))
      (node (ref "R104") (pin "2") (pinfunction "2_2") (pintype "passive"))
    )
    (net (code "115") (name "Net-(Q43-D)") (class "Default")
      (node (ref "JP70") (pin "1") (pinfunction "1_1") (pintype "passive"))
      (node (ref "Q43") (pin "3") (pinfunction "D_3") (pintype "bidirectional"))
    )
    (net (code "116") (name "Net-(Q43-G)") (class "Default")
      (node (ref "JP58") (pin "3") (pinfunction "3_3") (pintype "passive"))
      (node (ref "Q43") (pin "1") (pinfunction "G_1") (pintype "bidirectional"))
      (node (ref "Q44") (pin "3") (pinfunction "D_3") (pintype "bidirectional"))
      (node (ref "R106") (pin "2") (pinfunction "2_2") (pintype "passive"))
    )
    (net (code "117") (name "Net-(Q45-D)") (class "Default")
      (node (ref "JP71") (pin "1") (pinfunction "1_1") (pintype "passive"))
      (node (ref "Q45") (pin "3") (pinfunction "D_3") (pintype "bidirectional"))
    )
    (net (code "118") (name "Net-(Q45-G)") (class "Default")
      (node (ref "JP60") (pin "3") (pinfunction "3_3") (pintype "passive"))
      (node (ref "Q45") (pin "1") (pinfunction "G_1") (pintype "bidirectional"))
      (node (ref "Q46") (pin "3") (pinfunction "D_3") (pintype "bidirectional"))
      (node (ref "R108") (pin "2") (pinfunction "2_2") (pintype "passive"))
    )
    (net (code "119") (name "Net-(Q47-D)") (class "Default")
      (node (ref "JP72") (pin "1") (pinfunction "1_1") (pintype "passive"))
      (node (ref "Q47") (pin "3") (pinfunction "D_3") (pintype "bidirectional"))
    )
    (net (code "120") (name "Net-(Q47-G)") (class "Default")
      (node (ref "JP62") (pin "3") (pinfunction "3_3") (pintype "passive"))
      (node (ref "Q47") (pin "1") (pinfunction "G_1") (pintype "bidirectional"))
      (node (ref "Q48") (pin "3") (pinfunction "D_3") (pintype "bidirectional"))
      (node (ref "R110") (pin "2") (pinfunction "2_2") (pintype "passive"))
    )
    (net (code "121") (name "Net-(U1A-VIN+)") (class "Default")
      (node (ref "R11") (pin "1") (pinfunction "1_1") (pintype "passive"))
      (node (ref "R13") (pin "1") (pinfunction "1_1") (pintype "passive"))
      (node (ref "U1") (pin "3") (pinfunction "VIN+_3") (pintype "bidirectional"))
    )
    (net (code "122") (name "Net-(U1A-VIN-)") (class "Default")
      (node (ref "R10") (pin "1") (pinfunction "1_1") (pintype "passive"))
      (node (ref "R14") (pin "1") (pinfunction "1_1") (pintype "passive"))
      (node (ref "U1") (pin "2") (pinfunction "VIN-_2") (pintype "bidirectional"))
    )
    (net (code "123") (name "Net-(U1A-VOUT)") (class "Default")
      (node (ref "R14") (pin "2") (pinfunction "2_2") (pintype "passive"))
      (node (ref "R16") (pin "1") (pinfunction "1_1") (pintype "passive"))
      (node (ref "U1") (pin "1") (pinfunction "VOUT_1") (pintype "bidirectional"))
    )
    (net (code "124") (name "Net-(U1B-VIN+)") (class "Default")
      (node (ref "R28") (pin "1") (pinfunction "1_1") (pintype "passive"))
      (node (ref "R34") (pin "1") (pinfunction "1_1") (pintype "passive"))
      (node (ref "U1") (pin "5") (pinfunction "VIN+_5") (pintype "bidirectional"))
    )
    (net (code "125") (name "Net-(U1B-VIN-)") (class "Default")
      (node (ref "R29") (pin "1") (pinfunction "1_1") (pintype "passive"))
      (node (ref "R32") (pin "1") (pinfunction "1_1") (pintype "passive"))
      (node (ref "U1") (pin "6") (pinfunction "VIN-_6") (pintype "bidirectional"))
    )
    (net (code "126") (name "Net-(U1B-VOUT)") (class "Default")
      (node (ref "R34") (pin "2") (pinfunction "2_2") (pintype "passive"))
      (node (ref "R37") (pin "1") (pinfunction "1_1") (pintype "passive"))
      (node (ref "U1") (pin "7") (pinfunction "VOUT_7") (pintype "bidirectional"))
    )
    (net (code "127") (name "Net-(U4-FB)") (class "Default")
      (node (ref "R39") (pin "1") (pinfunction "1_1") (pintype "passive"))
      (node (ref "R40") (pin "2") (pinfunction "2_2") (pintype "passive"))
      (node (ref "U4") (pin "3") (pinfunction "FB_3") (pintype "bidirectional"))
    )
    (net (code "128") (name "Net-(U4-OC)") (class "Default")
      (node (ref "R35") (pin "2") (pinfunction "2_2") (pintype "passive"))
      (node (ref "U4") (pin "6") (pinfunction "OC_6") (pintype "bidirectional"))
    )
    (net (code "129") (name "Net-(U5-A12{slash}D+)") (class "Default")
      (node (ref "R42") (pin "2") (pinfunction "2_2") (pintype "passive"))
      (node (ref "U5") (pin "A12") (pinfunction "A12/D+_A12") (pintype "bidirectional"))
    )
    (net (code "130") (name "Net-(U7-A12{slash}D+)") (class "Default")
      (node (ref "R60") (pin "2") (pinfunction "2_2") (pintype "passive"))
      (node (ref "U7") (pin "A12") (pinfunction "A12/D+_A12") (pintype "bidirectional"))
    )
    (net (code "131") (name "Net-(U9-FB)") (class "Default")
      (node (ref "R66") (pin "1") (pinfunction "1_1") (pintype "passive"))
      (node (ref "R67") (pin "2") (pinfunction "2_2") (pintype "passive"))
      (node (ref "U9") (pin "3") (pinfunction "FB_3") (pintype "bidirectional"))
    )
    (net (code "132") (name "Net-(U9-OC)") (class "Default")
      (node (ref "R68") (pin "2") (pinfunction "2_2") (pintype "passive"))
      (node (ref "U9") (pin "6") (pinfunction "OC_6") (pintype "bidirectional"))
    )
    (net (code "133") (name "Net-(U10A-VIN+)") (class "Default")
      (node (ref "R69") (pin "1") (pinfunction "1_1") (pintype "passive"))
      (node (ref "R70") (pin "1") (pinfunction "1_1") (pintype "passive"))
      (node (ref "U10") (pin "3") (pinfunction "VIN+_3") (pintype "bidirectional"))
    )
    (net (code "134") (name "Net-(U10A-VIN-)") (class "Default")
      (node (ref "R71") (pin "1") (pinfunction "1_1") (pintype "passive"))
      (node (ref "R72") (pin "1") (pinfunction "1_1") (pintype "passive"))
      (node (ref "U10") (pin "2") (pinfunction "VIN-_2") (pintype "bidirectional"))
    )
    (net (code "135") (name "Net-(U10A-VOUT)") (class "Default")
      (node (ref "R72") (pin "2") (pinfunction "2_2") (pintype "passive"))
      (node (ref "R95") (pin "1") (pinfunction "1_1") (pintype "passive"))
      (node (ref "U10") (pin "1") (pinfunction "VOUT_1") (pintype "bidirectional"))
    )
    (net (code "136") (name "Net-(U10B-VIN+)") (class "Default")
      (node (ref "R92") (pin "1") (pinfunction "1_1") (pintype "passive"))
      (node (ref "R93") (pin "1") (pinfunction "1_1") (pintype "passive"))
      (node (ref "U10") (pin "5") (pinfunction "VIN+_5") (pintype "bidirectional"))
    )
    (net (code "137") (name "Net-(U10B-VIN-)") (class "Default")
      (node (ref "R90") (pin "1") (pinfunction "1_1") (pintype "passive"))
      (node (ref "R91") (pin "1") (pinfunction "1_1") (pintype "passive"))
      (node (ref "U10") (pin "6") (pinfunction "VIN-_6") (pintype "bidirectional"))
    )
    (net (code "138") (name "Net-(U10B-VOUT)") (class "Default")
      (node (ref "R93") (pin "2") (pinfunction "2_2") (pintype "passive"))
      (node (ref "R96") (pin "1") (pinfunction "1_1") (pintype "passive"))
      (node (ref "U10") (pin "7") (pinfunction "VOUT_7") (pintype "bidirectional"))
    )
    (net (code "139") (name "OD_1") (class "Default")
      (node (ref "Q24") (pin "1") (pinfunction "G_1") (pintype "bidirectional"))
      (node (ref "R56") (pin "2") (pinfunction "2_2") (pintype "passive"))
      (node (ref "U5") (pin "B12") (pinfunction "B12_B12") (pintype "bidirectional"))
    )
    (net (code "140") (name "OD_2") (class "Default")
      (node (ref "Q22") (pin "1") (pinfunction "G_1") (pintype "bidirectional"))
      (node (ref "R52") (pin "2") (pinfunction "2_2") (pintype "passive"))
      (node (ref "U5") (pin "B14") (pinfunction "B14_B14") (pintype "bidirectional"))
    )
    (net (code "141") (name "OD_3") (class "Default")
      (node (ref "Q20") (pin "1") (pinfunction "G_1") (pintype "bidirectional"))
      (node (ref "R50") (pin "2") (pinfunction "2_2") (pintype "passive"))
      (node (ref "U5") (pin "A8") (pinfunction "A8_A8") (pintype "bidirectional"))
    )
    (net (code "142") (name "OD_4") (class "Default")
      (node (ref "Q19") (pin "1") (pinfunction "G_1") (pintype "bidirectional"))
      (node (ref "R48") (pin "2") (pinfunction "2_2") (pintype "passive"))
      (node (ref "U5") (pin "A10") (pinfunction "A10_A10") (pintype "bidirectional"))
    )
    (net (code "143") (name "OD_5") (class "Default")
      (node (ref "Q17") (pin "1") (pinfunction "G_1") (pintype "bidirectional"))
      (node (ref "R44") (pin "2") (pinfunction "2_2") (pintype "passive"))
      (node (ref "U5") (pin "B3") (pinfunction "B3_B3") (pintype "bidirectional"))
    )
    (net (code "144") (name "OD_6") (class "Default")
      (node (ref "Q15") (pin "1") (pinfunction "G_1") (pintype "bidirectional"))
      (node (ref "R41") (pin "2") (pinfunction "2_2") (pintype "passive"))
      (node (ref "U5") (pin "B5") (pinfunction "B5_B5") (pintype "bidirectional"))
    )
    (net (code "145") (name "OD_7") (class "Default")
      (node (ref "Q32") (pin "1") (pinfunction "G_1") (pintype "bidirectional"))
      (node (ref "R84") (pin "2") (pinfunction "2_2") (pintype "passive"))
      (node (ref "U7") (pin "B12") (pinfunction "B12_B12") (pintype "bidirectional"))
    )
    (net (code "146") (name "OD_8") (class "Default")
      (node (ref "Q31") (pin "1") (pinfunction "G_1") (pintype "bidirectional"))
      (node (ref "R83") (pin "2") (pinfunction "2_2") (pintype "passive"))
      (node (ref "U7") (pin "B14") (pinfunction "B14_B14") (pintype "bidirectional"))
    )
    (net (code "147") (name "OD_9") (class "Default")
      (node (ref "Q30") (pin "1") (pinfunction "G_1") (pintype "bidirectional"))
      (node (ref "R82") (pin "2") (pinfunction "2_2") (pintype "passive"))
      (node (ref "U7") (pin "A8") (pinfunction "A8_A8") (pintype "bidirectional"))
    )
    (net (code "148") (name "OD_10") (class "Default")
      (node (ref "Q29") (pin "1") (pinfunction "G_1") (pintype "bidirectional"))
      (node (ref "R81") (pin "2") (pinfunction "2_2") (pintype "passive"))
      (node (ref "U7") (pin "A10") (pinfunction "A10_A10") (pintype "bidirectional"))
    )
    (net (code "149") (name "OD_11") (class "Default")
      (node (ref "Q28") (pin "1") (pinfunction "G_1") (pintype "bidirectional"))
      (node (ref "R80") (pin "2") (pinfunction "2_2") (pintype "passive"))
      (node (ref "U7") (pin "B3") (pinfunction "B3_B3") (pintype "bidirectional"))
    )
    (net (code "150") (name "OD_12") (class "Default")
      (node (ref "Q25") (pin "1") (pinfunction "G_1") (pintype "bidirectional"))
      (node (ref "R79") (pin "2") (pinfunction "2_2") (pintype "passive"))
      (node (ref "U7") (pin "B5") (pinfunction "B5_B5") (pintype "bidirectional"))
    )
    (net (code "151") (name "RLY_1") (class "Default")
      (node (ref "Q2") (pin "1") (pinfunction "G_1") (pintype "bidirectional"))
      (node (ref "R2") (pin "2") (pinfunction "2_2") (pintype "passive"))
      (node (ref "U5") (pin "B13") (pinfunction "B13_B13") (pintype "bidirectional"))
    )
    (net (code "152") (name "RLY_2") (class "Default")
      (node (ref "Q6") (pin "1") (pinfunction "G_1") (pintype "bidirectional"))
      (node (ref "R12") (pin "2") (pinfunction "2_2") (pintype "passive"))
      (node (ref "U5") (pin "B15") (pinfunction "B15_B15") (pintype "bidirectional"))
    )
    (net (code "153") (name "RLY_3") (class "Default")
      (node (ref "Q8") (pin "1") (pinfunction "G_1") (pintype "bidirectional"))
      (node (ref "R17") (pin "2") (pinfunction "2_2") (pintype "passive"))
      (node (ref "U5") (pin "A9") (pinfunction "A9_A9") (pintype "bidirectional"))
    )
    (net (code "154") (name "RLY_4") (class "Default")
      (node (ref "Q12") (pin "1") (pinfunction "G_1") (pintype "bidirectional"))
      (node (ref "R23") (pin "2") (pinfunction "2_2") (pintype "passive"))
      (node (ref "U5") (pin "A15") (pinfunction "A15_A15") (pintype "bidirectional"))
    )
    (net (code "155") (name "RLY_5") (class "Default")
      (node (ref "Q14") (pin "1") (pinfunction "G_1") (pintype "bidirectional"))
      (node (ref "R36") (pin "2") (pinfunction "2_2") (pintype "passive"))
      (node (ref "U5") (pin "B4") (pinfunction "B4_B4") (pintype "bidirectional"))
    )
    (net (code "156") (name "RLY_6") (class "Default")
      (node (ref "Q18") (pin "1") (pinfunction "G_1") (pintype "bidirectional"))
      (node (ref "R45") (pin "2") (pinfunction "2_2") (pintype "passive"))
      (node (ref "U5") (pin "B6") (pinfunction "B6_B6") (pintype "bidirectional"))
    )
    (net (code "157") (name "RLY_7") (class "Default")
      (node (ref "Q23") (pin "1") (pinfunction "G_1") (pintype "bidirectional"))
      (node (ref "R53") (pin "2") (pinfunction "2_2") (pintype "passive"))
      (node (ref "U5") (pin "B7") (pinfunction "B7_B7") (pintype "bidirectional"))
    )
    (net (code "158") (name "RLY_8") (class "Default")
      (node (ref "Q36") (pin "1") (pinfunction "G_1") (pintype "bidirectional"))
      (node (ref "R97") (pin "2") (pinfunction "2_2") (pintype "passive"))
      (node (ref "U7") (pin "B13") (pinfunction "B13_B13") (pintype "bidirectional"))
    )
    (net (code "159") (name "RLY_9") (class "Default")
      (node (ref "Q38") (pin "1") (pinfunction "G_1") (pintype "bidirectional"))
      (node (ref "R99") (pin "2") (pinfunction "2_2") (pintype "passive"))
      (node (ref "U7") (pin "B15") (pinfunction "B15_B15") (pintype "bidirectional"))
    )
    (net (code "160") (name "RLY_10") (class "Default")
      (node (ref "Q40") (pin "1") (pinfunction "G_1") (pintype "bidirectional"))
      (node (ref "R101") (pin "2") (pinfunction "2_2") (pintype "passive"))
      (node (ref "U7") (pin "A9") (pinfunction "A9_A9") (pintype "bidirectional"))
    )
    (net (code "161") (name "RLY_11") (class "Default")
      (node (ref "Q42") (pin "1") (pinfunction "G_1") (pintype "bidirectional"))
      (node (ref "R103") (pin "2") (pinfunction "2_2") (pintype "passive"))
      (node (ref "U7") (pin "A15") (pinfunction "A15_A15") (pintype "bidirectional"))
    )
    (net (code "162") (name "RLY_12") (class "Default")
      (node (ref "Q44") (pin "1") (pinfunction "G_1") (pintype "bidirectional"))
      (node (ref "R105") (pin "2") (pinfunction "2_2") (pintype "passive"))
      (node (ref "U7") (pin "B4") (pinfunction "B4_B4") (pintype "bidirectional"))
    )
    (net (code "163") (name "RLY_13") (class "Default")
      (node (ref "Q46") (pin "1") (pinfunction "G_1") (pintype "bidirectional"))
      (node (ref "R107") (pin "2") (pinfunction "2_2") (pintype "passive"))
      (node (ref "U7") (pin "B6") (pinfunction "B6_B6") (pintype "bidirectional"))
    )
    (net (code "164") (name "RLY_14") (class "Default")
      (node (ref "Q48") (pin "1") (pinfunction "G_1") (pintype "bidirectional"))
      (node (ref "R109") (pin "2") (pinfunction "2_2") (pintype "passive"))
      (node (ref "U7") (pin "B7") (pinfunction "B7_B7") (pintype "bidirectional"))
    )
    (net (code "165") (name "SSRX+") (class "Default")
      (node (ref "CON3") (pin "6-SSRX+") (pinfunction "SSRX+_6-SSRX+") (pintype "bidirectional"))
      (node (ref "CON4") (pin "6-SSRX+") (pinfunction "SSRX+_6-SSRX+") (pintype "bidirectional"))
    )
    (net (code "166") (name "SSRX+1") (class "Default")
      (node (ref "CON7") (pin "6-SSRX+") (pinfunction "SSRX+_6-SSRX+") (pintype "bidirectional"))
      (node (ref "CON8") (pin "6-SSRX+") (pinfunction "SSRX+_6-SSRX+") (pintype "bidirectional"))
    )
    (net (code "167") (name "SSRX-") (class "Default")
      (node (ref "CON3") (pin "5-SSRX-") (pinfunction "SSRX-_5-SSRX-") (pintype "bidirectional"))
      (node (ref "CON4") (pin "5-SSRX-") (pinfunction "SSRX-_5-SSRX-") (pintype "bidirectional"))
    )
    (net (code "168") (name "SSRX-1") (class "Default")
      (node (ref "CON7") (pin "5-SSRX-") (pinfunction "SSRX-_5-SSRX-") (pintype "bidirectional"))
      (node (ref "CON8") (pin "5-SSRX-") (pinfunction "SSRX-_5-SSRX-") (pintype "bidirectional"))
    )
    (net (code "169") (name "SSTX+") (class "Default")
      (node (ref "CON3") (pin "9-SSTX+") (pinfunction "SSTX+_9-SSTX+") (pintype "bidirectional"))
      (node (ref "CON4") (pin "9-SSTX+") (pinfunction "SSTX+_9-SSTX+") (pintype "bidirectional"))
    )
    (net (code "170") (name "SSTX+1") (class "Default")
      (node (ref "CON7") (pin "9-SSTX+") (pinfunction "SSTX+_9-SSTX+") (pintype "bidirectional"))
      (node (ref "CON8") (pin "9-SSTX+") (pinfunction "SSTX+_9-SSTX+") (pintype "bidirectional"))
    )
    (net (code "171") (name "SSTX-") (class "Default")
      (node (ref "CON3") (pin "8-SSTX-") (pinfunction "SSTX-_8-SSTX-") (pintype "bidirectional"))
      (node (ref "CON4") (pin "8-SSTX-") (pinfunction "SSTX-_8-SSTX-") (pintype "bidirectional"))
    )
    (net (code "172") (name "SSTX-1") (class "Default")
      (node (ref "CON7") (pin "8-SSTX-") (pinfunction "SSTX-_8-SSTX-") (pintype "bidirectional"))
      (node (ref "CON8") (pin "8-SSTX-") (pinfunction "SSTX-_8-SSTX-") (pintype "bidirectional"))
    )
    (net (code "173") (name "USB2-EN") (class "Default")
      (node (ref "Q4") (pin "1") (pinfunction "G_1") (pintype "bidirectional"))
      (node (ref "R1") (pin "1") (pinfunction "1_1") (pintype "passive"))
      (node (ref "U5") (pin "B11") (pinfunction "B11_B11") (pintype "bidirectional"))
    )
    (net (code "174") (name "USB2-EN1") (class "Default")
      (node (ref "Q27") (pin "1") (pinfunction "G_1") (pintype "bidirectional"))
      (node (ref "R111") (pin "1") (pinfunction "1_1") (pintype "passive"))
      (node (ref "U7") (pin "B11") (pinfunction "B11_B11") (pintype "bidirectional"))
    )
    (net (code "175") (name "USB2-ISNS") (class "Default")
      (node (ref "C4") (pin "1") (pinfunction "1_1") (pintype "passive"))
      (node (ref "R16") (pin "2") (pinfunction "2_2") (pintype "passive"))
      (node (ref "U5") (pin "B1") (pinfunction "B1_B1") (pintype "bidirectional"))
    )
    (net (code "176") (name "USB2-ISNS1") (class "Default")
      (node (ref "C34") (pin "1") (pinfunction "1_1") (pintype "passive"))
      (node (ref "R95") (pin "2") (pinfunction "2_2") (pintype "passive"))
      (node (ref "U7") (pin "B1") (pinfunction "B1_B1") (pintype "bidirectional"))
    )
    (net (code "177") (name "USB2-TSNS") (class "Default")
      (node (ref "C3") (pin "1") (pinfunction "1_1") (pintype "passive"))
      (node (ref "J1") (pin "2") (pinfunction "2_2") (pintype "passive"))
      (node (ref "R9") (pin "1") (pinfunction "1_1") (pintype "passive"))
      (node (ref "U5") (pin "A3") (pinfunction "A3_A3") (pintype "bidirectional"))
    )
    (net (code "178") (name "USB2-TSNS1") (class "Default")
      (node (ref "C26") (pin "1") (pinfunction "1_1") (pintype "passive"))
      (node (ref "J3") (pin "2") (pinfunction "2_2") (pintype "passive"))
      (node (ref "R59") (pin "1") (pinfunction "1_1") (pintype "passive"))
      (node (ref "U7") (pin "A3") (pinfunction "A3_A3") (pintype "bidirectional"))
    )
    (net (code "179") (name "USB2-VCC-SW") (class "Default")
      (node (ref "CON1") (pin "1-5V") (pinfunction "VCC_1-5V") (pintype "bidirectional"))
      (node (ref "Q3") (pin "5") (pinfunction "D_5") (pintype "bidirectional"))
      (node (ref "Q3") (pin "6") (pinfunction "D_6") (pintype "bidirectional"))
      (node (ref "Q3") (pin "7") (pinfunction "D_7") (pintype "bidirectional"))
      (node (ref "Q3") (pin "8") (pinfunction "D_8") (pintype "bidirectional"))
      (node (ref "R3") (pin "2") (pinfunction "2_2") (pintype "passive"))
    )
    (net (code "180") (name "USB2-VCC-SW1") (class "Default")
      (node (ref "CON6") (pin "1-5V") (pinfunction "VCC_1-5V") (pintype "bidirectional"))
      (node (ref "Q26") (pin "5") (pinfunction "D_5") (pintype "bidirectional"))
      (node (ref "Q26") (pin "6") (pinfunction "D_6") (pintype "bidirectional"))
      (node (ref "Q26") (pin "7") (pinfunction "D_7") (pintype "bidirectional"))
      (node (ref "Q26") (pin "8") (pinfunction "D_8") (pintype "bidirectional"))
      (node (ref "R64") (pin "2") (pinfunction "2_2") (pintype "passive"))
    )
    (net (code "181") (name "USB2-VSNS") (class "Default")
      (node (ref "C2") (pin "1") (pinfunction "1_1") (pintype "passive"))
      (node (ref "R3") (pin "1") (pinfunction "1_1") (pintype "passive"))
      (node (ref "R4") (pin "2") (pinfunction "2_2") (pintype "passive"))
      (node (ref "U5") (pin "B0") (pinfunction "B0_B0") (pintype "bidirectional"))
    )
    (net (code "182") (name "USB2-VSNS1") (class "Default")
      (node (ref "C36") (pin "1") (pinfunction "1_1") (pintype "passive"))
      (node (ref "R64") (pin "1") (pinfunction "1_1") (pintype "passive"))
      (node (ref "R65") (pin "2") (pinfunction "2_2") (pintype "passive"))
      (node (ref "U7") (pin "B0") (pinfunction "B0_B0") (pintype "bidirectional"))
    )
    (net (code "183") (name "USB2VIN") (class "Default")
      (node (ref "CON2") (pin "1-VCC") (pinfunction "VCC_1-VCC") (pintype "bidirectional"))
      (node (ref "D2") (pin "A") (pinfunction "ANODE_A") (pintype "passive"))
      (node (ref "D9") (pin "A") (pinfunction "ANODE_A") (pintype "passive"))
      (node (ref "R11") (pin "2") (pinfunction "2_2") (pintype "passive"))
      (node (ref "R7") (pin "2") (pinfunction "2_2") (pintype "passive"))
      (node (ref "R8") (pin "2") (pinfunction "2_2") (pintype "passive"))
    )
    (net (code "184") (name "USB2VIN1") (class "Default")
      (node (ref "CON5") (pin "1-VCC") (pinfunction "VCC_1-VCC") (pintype "bidirectional"))
      (node (ref "D15") (pin "A") (pinfunction "ANODE_A") (pintype "passive"))
      (node (ref "D18") (pin "A") (pinfunction "ANODE_A") (pintype "passive"))
      (node (ref "R61") (pin "2") (pinfunction "2_2") (pintype "passive"))
      (node (ref "R69") (pin "2") (pinfunction "2_2") (pintype "passive"))
      (node (ref "R73") (pin "2") (pinfunction "2_2") (pintype "passive"))
    )
    (net (code "185") (name "USB3-EN") (class "Default")
      (node (ref "Q10") (pin "1") (pinfunction "G_1") (pintype "bidirectional"))
      (node (ref "R20") (pin "1") (pinfunction "1_1") (pintype "passive"))
      (node (ref "U5") (pin "B10") (pinfunction "B10_B10") (pintype "bidirectional"))
    )
    (net (code "186") (name "USB3-EN1") (class "Default")
      (node (ref "Q35") (pin "1") (pinfunction "G_1") (pintype "bidirectional"))
      (node (ref "R112") (pin "1") (pinfunction "1_1") (pintype "passive"))
      (node (ref "U7") (pin "B10") (pinfunction "B10_B10") (pintype "bidirectional"))
    )
    (net (code "187") (name "USB3-ISNS") (class "Default")
      (node (ref "C14") (pin "1") (pinfunction "1_1") (pintype "passive"))
      (node (ref "R37") (pin "2") (pinfunction "2_2") (pintype "passive"))
      (node (ref "U5") (pin "A7") (pinfunction "A7_A7") (pintype "bidirectional"))
    )
    (net (code "188") (name "USB3-ISNS1") (class "Default")
      (node (ref "C35") (pin "1") (pinfunction "1_1") (pintype "passive"))
      (node (ref "R96") (pin "2") (pinfunction "2_2") (pintype "passive"))
      (node (ref "U7") (pin "A7") (pinfunction "A7_A7") (pintype "bidirectional"))
    )
    (net (code "189") (name "USB3-TSNS") (class "Default")
      (node (ref "C11") (pin "1") (pinfunction "1_1") (pintype "passive"))
      (node (ref "J2") (pin "2") (pinfunction "2_2") (pintype "passive"))
      (node (ref "R30") (pin "1") (pinfunction "1_1") (pintype "passive"))
      (node (ref "U5") (pin "A2") (pinfunction "A2_A2") (pintype "bidirectional"))
    )
    (net (code "190") (name "USB3-TSNS1") (class "Default")
      (node (ref "C33") (pin "1") (pinfunction "1_1") (pintype "passive"))
      (node (ref "J4") (pin "2") (pinfunction "2_2") (pintype "passive"))
      (node (ref "R85") (pin "1") (pinfunction "1_1") (pintype "passive"))
      (node (ref "U7") (pin "A2") (pinfunction "A2_A2") (pintype "bidirectional"))
    )
    (net (code "191") (name "USB3-VCC-SW") (class "Default")
      (node (ref "CON3") (pin "1-VBUS") (pinfunction "VBUS_1-VBUS") (pintype "bidirectional"))
      (node (ref "Q9") (pin "5") (pinfunction "D_5") (pintype "bidirectional"))
      (node (ref "Q9") (pin "6") (pinfunction "D_6") (pintype "bidirectional"))
      (node (ref "Q9") (pin "7") (pinfunction "D_7") (pintype "bidirectional"))
      (node (ref "Q9") (pin "8") (pinfunction "D_8") (pintype "bidirectional"))
      (node (ref "R21") (pin "2") (pinfunction "2_2") (pintype "passive"))
    )
    (net (code "192") (name "USB3-VCC-SW1") (class "Default")
      (node (ref "CON8") (pin "1-VBUS") (pinfunction "VBUS_1-VBUS") (pintype "bidirectional"))
      (node (ref "Q34") (pin "5") (pinfunction "D_5") (pintype "bidirectional"))
      (node (ref "Q34") (pin "6") (pinfunction "D_6") (pintype "bidirectional"))
      (node (ref "Q34") (pin "7") (pinfunction "D_7") (pintype "bidirectional"))
      (node (ref "Q34") (pin "8") (pinfunction "D_8") (pintype "bidirectional"))
      (node (ref "R88") (pin "2") (pinfunction "2_2") (pintype "passive"))
    )
    (net (code "193") (name "USB3-VSNS") (class "Default")
      (node (ref "C6") (pin "1") (pinfunction "1_1") (pintype "passive"))
      (node (ref "R21") (pin "1") (pinfunction "1_1") (pintype "passive"))
      (node (ref "R22") (pin "2") (pinfunction "2_2") (pintype "passive"))
      (node (ref "U5") (pin "A6") (pinfunction "A6_A6") (pintype "bidirectional"))
    )
    (net (code "194") (name "USB3-VSNS1") (class "Default")
      (node (ref "C37") (pin "1") (pinfunction "1_1") (pintype "passive"))
      (node (ref "R88") (pin "1") (pinfunction "1_1") (pintype "passive"))
      (node (ref "R89") (pin "2") (pinfunction "2_2") (pintype "passive"))
      (node (ref "U7") (pin "A6") (pinfunction "A6_A6") (pintype "bidirectional"))
    )
    (net (code "195") (name "USB3VIN") (class "Default")
      (node (ref "CON4") (pin "1-VBUS") (pinfunction "VBUS_1-VBUS") (pintype "bidirectional"))
      (node (ref "D3") (pin "A") (pinfunction "ANODE_A") (pintype "passive"))
      (node (ref "D8") (pin "A") (pinfunction "ANODE_A") (pintype "passive"))
      (node (ref "R26") (pin "2") (pinfunction "2_2") (pintype "passive"))
      (node (ref "R27") (pin "2") (pinfunction "2_2") (pintype "passive"))
      (node (ref "R29") (pin "2") (pinfunction "2_2") (pintype "passive"))
    )
    (net (code "196") (name "USB3VIN1") (class "Default")
      (node (ref "CON7") (pin "1-VBUS") (pinfunction "VBUS_1-VBUS") (pintype "bidirectional"))
      (node (ref "D16") (pin "A") (pinfunction "ANODE_A") (pintype "passive"))
      (node (ref "D19") (pin "A") (pinfunction "ANODE_A") (pintype "passive"))
      (node (ref "R86") (pin "2") (pinfunction "2_2") (pintype "passive"))
      (node (ref "R90") (pin "2") (pinfunction "2_2") (pintype "passive"))
      (node (ref "R94") (pin "2") (pinfunction "2_2") (pintype "passive"))
    )
    (net (code "197") (name "USBBPIN") (class "Default")
      (node (ref "C16") (pin "1") (pinfunction "1_1") (pintype "passive"))
      (node (ref "C5") (pin "1") (pinfunction "1_1") (pintype "passive"))
      (node (ref "D4") (pin "A") (pinfunction "ANODE_A") (pintype "passive"))
      (node (ref "D7") (pin "A") (pinfunction "ANODE_A") (pintype "passive"))
      (node (ref "JP18") (pin "1") (pinfunction "1_1") (pintype "passive"))
      (node (ref "JP21") (pin "1") (pinfunction "1_1") (pintype "passive"))
      (node (ref "JP24") (pin "1") (pinfunction "1_1") (pintype "passive"))
      (node (ref "JP28") (pin "3") (pinfunction "3_3") (pintype "passive"))
      (node (ref "JP30") (pin "1") (pinfunction "1_1") (pintype "passive"))
      (node (ref "JP33") (pin "1") (pinfunction "1_1") (pintype "passive"))
      (node (ref "JP36") (pin "1") (pinfunction "1_1") (pintype "passive"))
      (node (ref "R18") (pin "1") (pinfunction "1_1") (pintype "passive"))
      (node (ref "U3") (pin "3") (pinfunction "VIN_3") (pintype "bidirectional"))
      (node (ref "U5") (pin "5V") (pinfunction "5V_5V") (pintype "bidirectional"))
    )
    (net (code "198") (name "USBBPIN1") (class "Default")
      (node (ref "C23") (pin "1") (pinfunction "1_1") (pintype "passive"))
      (node (ref "C25") (pin "1") (pinfunction "1_1") (pintype "passive"))
      (node (ref "D17") (pin "A") (pinfunction "ANODE_A") (pintype "passive"))
      (node (ref "D20") (pin "A") (pinfunction "ANODE_A") (pintype "passive"))
      (node (ref "JP38") (pin "1") (pinfunction "1_1") (pintype "passive"))
      (node (ref "JP40") (pin "1") (pinfunction "1_1") (pintype "passive"))
      (node (ref "JP42") (pin "1") (pinfunction "1_1") (pintype "passive"))
      (node (ref "JP44") (pin "1") (pinfunction "1_1") (pintype "passive"))
      (node (ref "JP46") (pin "1") (pinfunction "1_1") (pintype "passive"))
      (node (ref "JP48") (pin "1") (pinfunction "1_1") (pintype "passive"))
      (node (ref "JP65") (pin "3") (pinfunction "3_3") (pintype "passive"))
      (node (ref "R58") (pin "1") (pinfunction "1_1") (pintype "passive"))
      (node (ref "U7") (pin "5V") (pinfunction "5V_5V") (pintype "bidirectional"))
      (node (ref "U8") (pin "3") (pinfunction "VIN_3") (pintype "bidirectional"))
    )
    (net (code "199") (name "VUSBMAX") (class "Default")
      (node (ref "C1") (pin "1") (pinfunction "1_1") (pintype "passive"))
      (node (ref "D2") (pin "K") (pinfunction "CATHODE_K") (pintype "passive"))
      (node (ref "D3") (pin "K") (pinfunction "CATHODE_K") (pintype "passive"))
      (node (ref "D4") (pin "K") (pinfunction "CATHODE_K") (pintype "passive"))
      (node (ref "U1") (pin "8") (pinfunction "VCC_8") (pintype "power_in"))
    )
    (net (code "200") (name "VUSBMAX1") (class "Default")
      (node (ref "C20") (pin "1") (pinfunction "1_1") (pintype "passive"))
      (node (ref "D15") (pin "K") (pinfunction "CATHODE_K") (pintype "passive"))
      (node (ref "D16") (pin "K") (pinfunction "CATHODE_K") (pintype "passive"))
      (node (ref "D17") (pin "K") (pinfunction "CATHODE_K") (pintype "passive"))
      (node (ref "U10") (pin "8") (pinfunction "VCC_8") (pintype "power_in"))
    )
    (net (code "201") (name "unconnected-(CON2-ID-Pad4-ID)") (class "Default")
      (node (ref "CON2") (pin "4-ID") (pinfunction "ID_4-ID") (pintype "bidirectional"))
    )
    (net (code "202") (name "unconnected-(CON5-ID-Pad4-ID)") (class "Default")
      (node (ref "CON5") (pin "4-ID") (pinfunction "ID_4-ID") (pintype "bidirectional"))
    )
    (net (code "203") (name "unconnected-(U5-PadRST)") (class "Default")
      (node (ref "U5") (pin "RST") (pinfunction "RST_RST") (pintype "bidirectional"))
    )
    (net (code "204") (name "unconnected-(U5-VB-PadVBAT)") (class "Default")
      (node (ref "U5") (pin "VBAT") (pinfunction "VB_VBAT") (pintype "bidirectional"))
    )
    (net (code "205") (name "unconnected-(U7-PadRST)") (class "Default")
      (node (ref "U7") (pin "RST") (pinfunction "RST_RST") (pintype "bidirectional"))
    )
    (net (code "206") (name "unconnected-(U7-VB-PadVBAT)") (class "Default")
      (node (ref "U7") (pin "VBAT") (pinfunction "VB_VBAT") (pintype "bidirectional"))
    )
  )
)
